# NHK2016mother.net
KiCad netlist of a schematic drawn in EAGLE
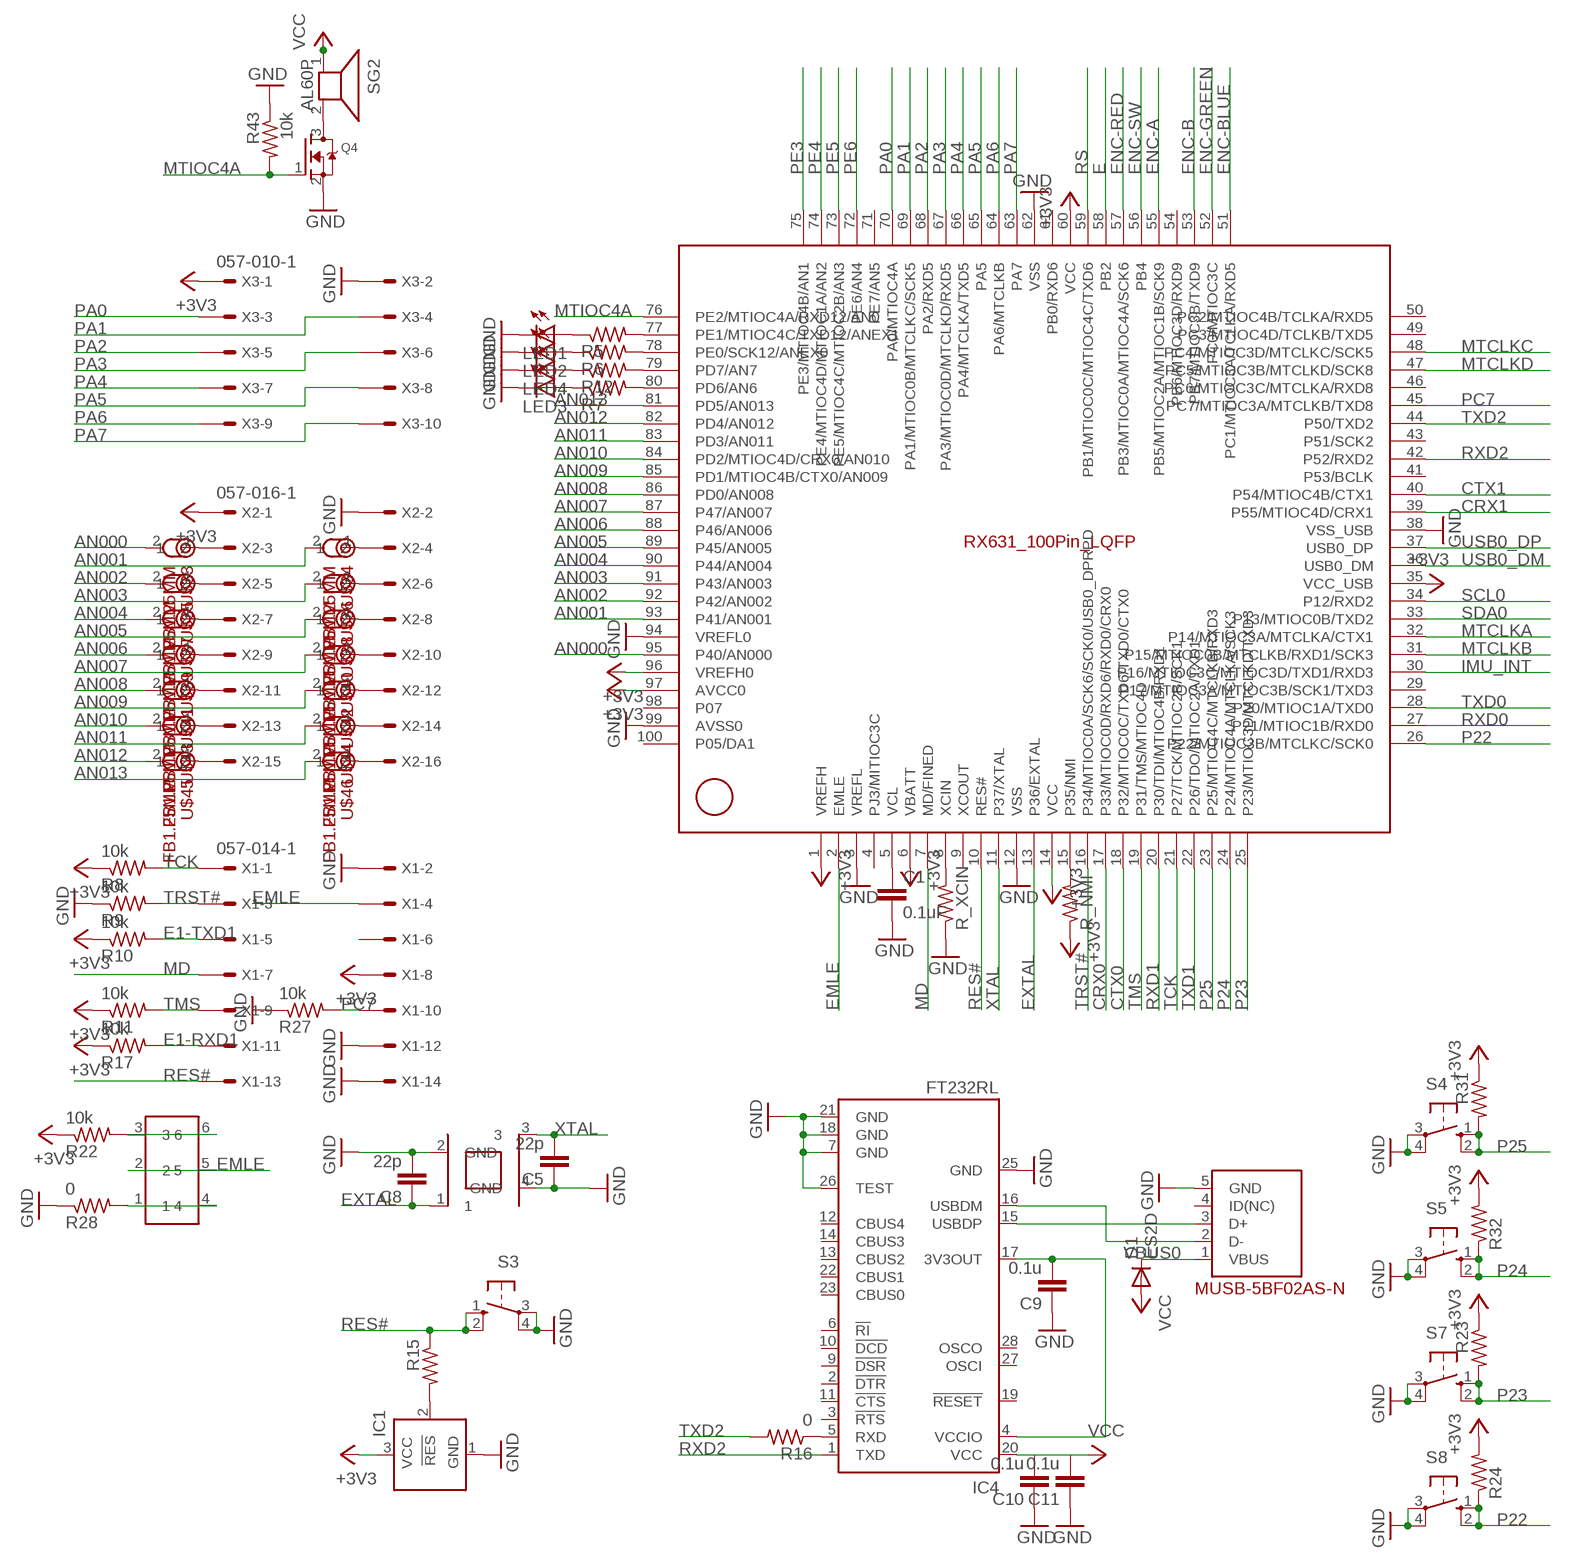
[diagram p0: schematic, sheet 1, part 1 of 2]
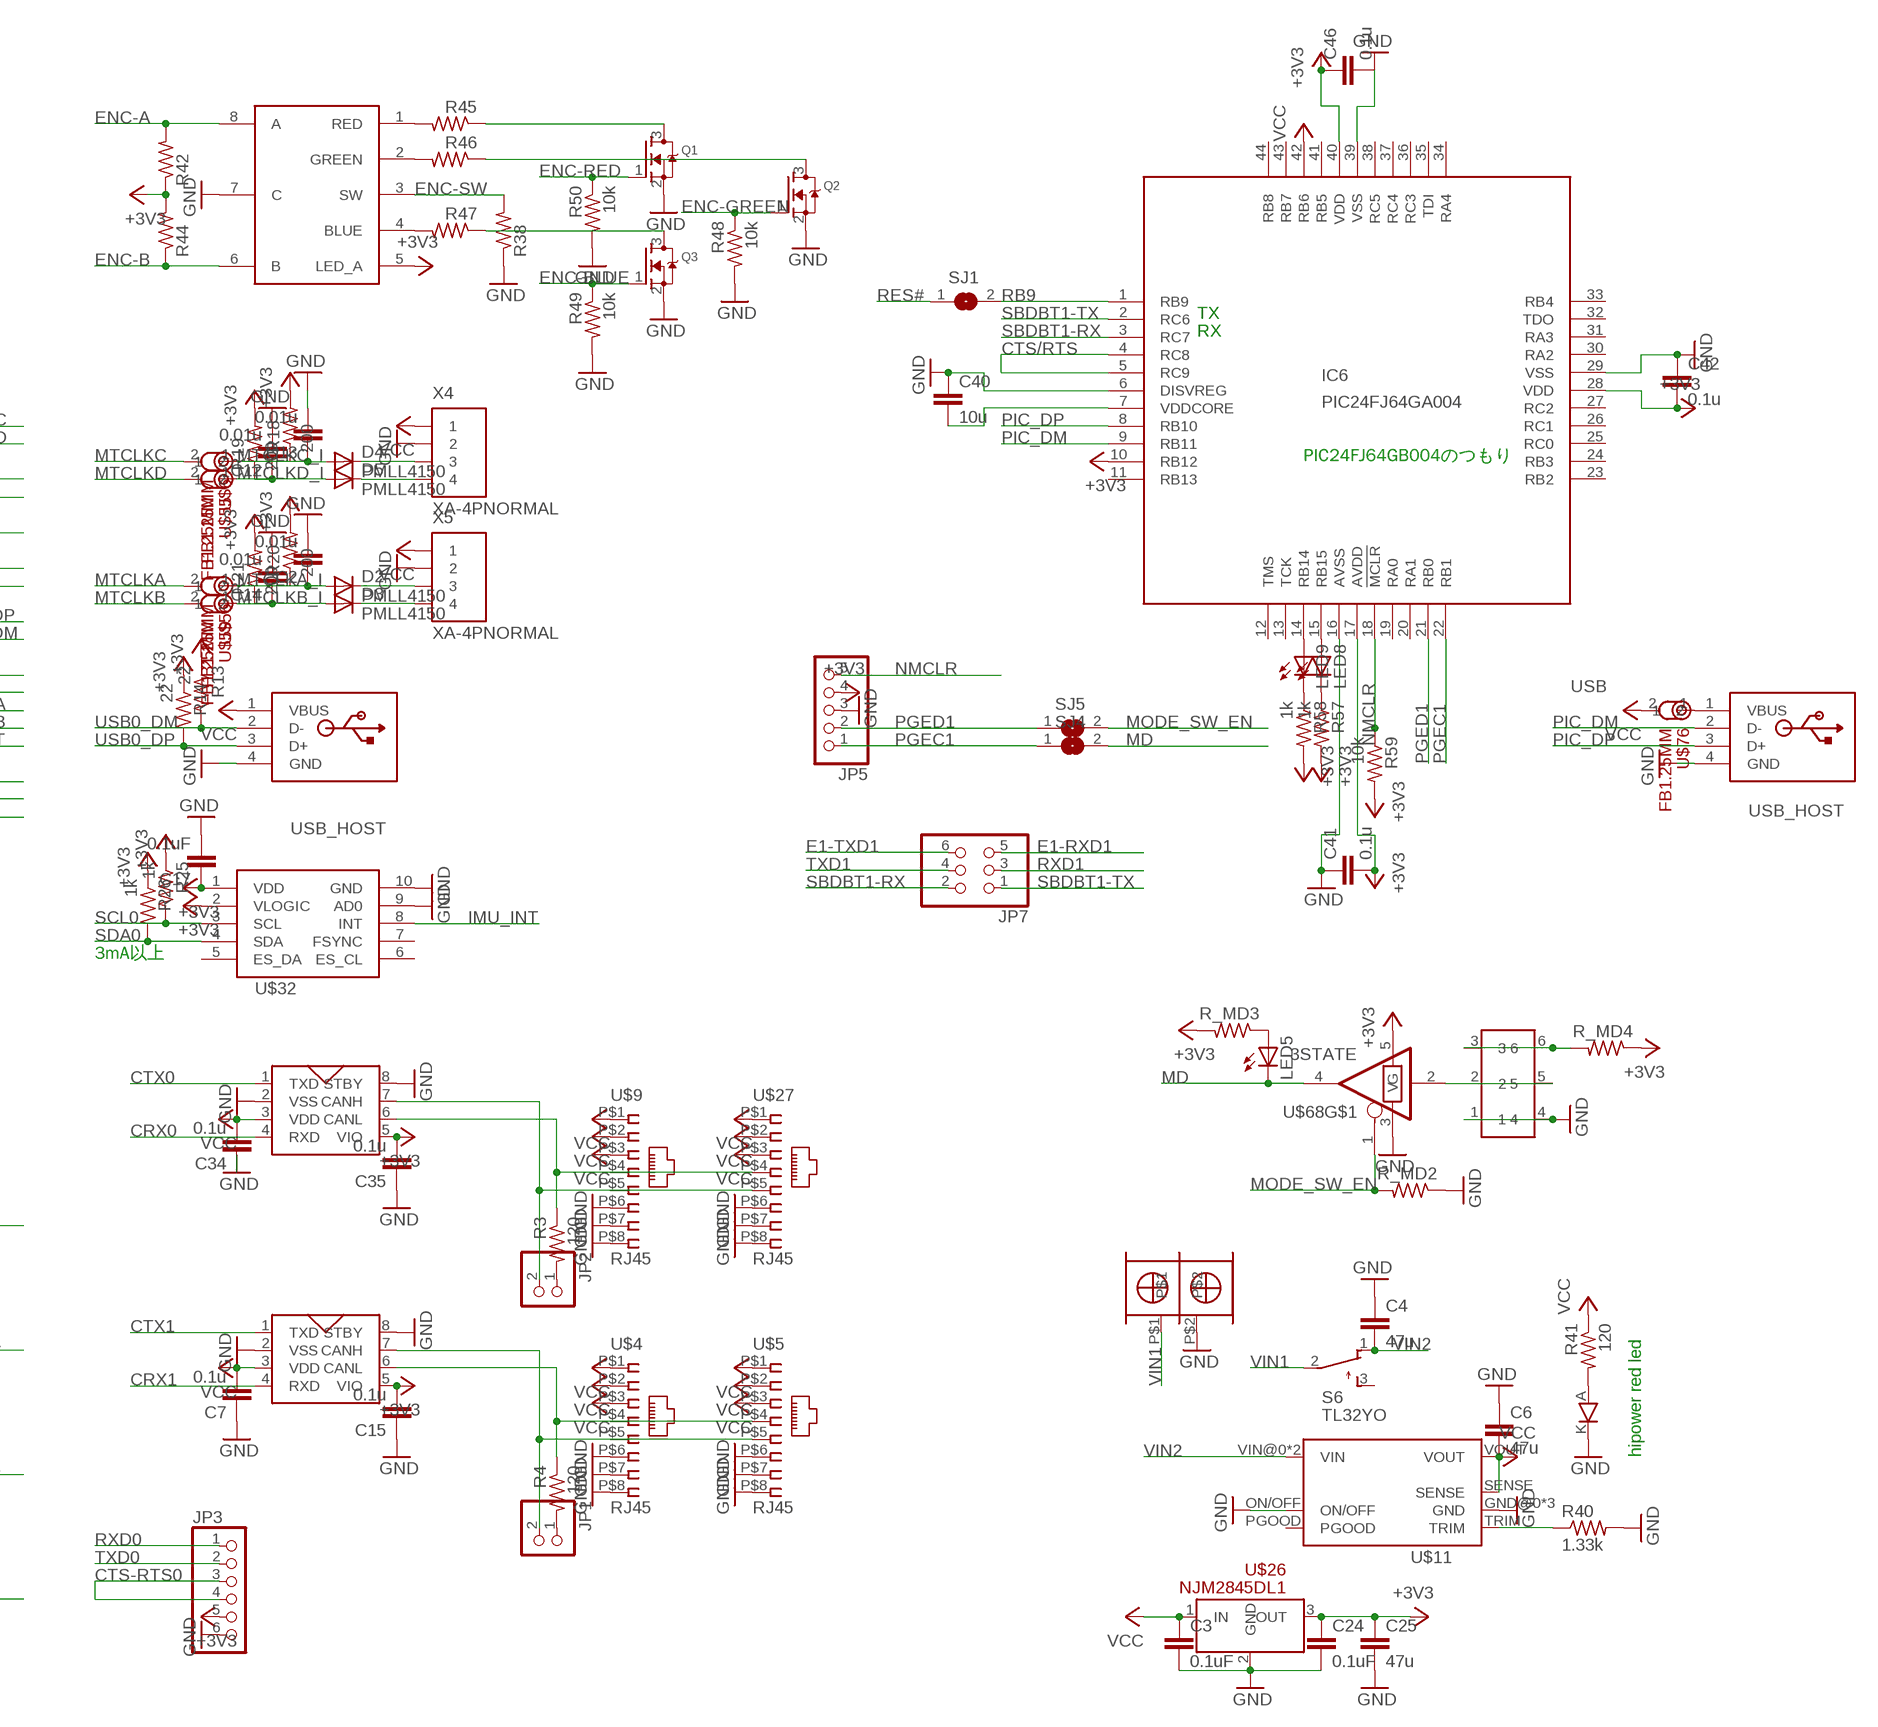
[diagram p1: schematic, sheet 1, part 2 of 2]

(export (version "E")
  (design (tool "Eeschema 10.0.6"))
  (components
    (comp (ref "C1")
      (value "0.1uF")
      (footprint "eagle-import:C0603K")
      (libsource (lib "eagle-import") (part "C-EUC0603K"))
    )
    (comp (ref "C2")
      (value "0.01u")
      (footprint "eagle-import:C0402")
      (libsource (lib "eagle-import") (part "C-EUC0402"))
    )
    (comp (ref "C3")
      (value "0.1uF")
      (footprint "eagle-import:C0603K")
      (libsource (lib "eagle-import") (part "C-EUC0603K"))
    )
    (comp (ref "C4")
      (value "47u")
      (footprint "eagle-import:C3225")
      (libsource (lib "eagle-import") (part "C-EUC3225"))
    )
    (comp (ref "C5")
      (value "22p")
      (footprint "eagle-import:C0603K")
      (libsource (lib "eagle-import") (part "C-EUC0603K"))
    )
    (comp (ref "C6")
      (value "47u")
      (footprint "eagle-import:C3225")
      (libsource (lib "eagle-import") (part "C-EUC3225"))
    )
    (comp (ref "C7")
      (value "0.1u")
      (footprint "eagle-import:C0402")
      (libsource (lib "eagle-import") (part "C-EUC0402"))
    )
    (comp (ref "C8")
      (value "22p")
      (footprint "eagle-import:C0603K")
      (libsource (lib "eagle-import") (part "C-EUC0603K"))
    )
    (comp (ref "C9")
      (value "0.1u")
      (footprint "eagle-import:C0402")
      (libsource (lib "eagle-import") (part "C-EUC0402"))
    )
    (comp (ref "C10")
      (value "0.1u")
      (footprint "eagle-import:C0402")
      (libsource (lib "eagle-import") (part "C-EUC0402"))
    )
    (comp (ref "C11")
      (value "0.1u")
      (footprint "eagle-import:C0402")
      (libsource (lib "eagle-import") (part "C-EUC0402"))
    )
    (comp (ref "C12")
      (value "0.01u")
      (footprint "eagle-import:C0402")
      (libsource (lib "eagle-import") (part "C-EUC0402"))
    )
    (comp (ref "C13")
      (value "0.01u")
      (footprint "eagle-import:C0402")
      (libsource (lib "eagle-import") (part "C-EUC0402"))
    )
    (comp (ref "C14")
      (value "0.01u")
      (footprint "eagle-import:C0402")
      (libsource (lib "eagle-import") (part "C-EUC0402"))
    )
    (comp (ref "C15")
      (value "0.1u")
      (footprint "eagle-import:C0402")
      (libsource (lib "eagle-import") (part "C-EUC0402"))
    )
    (comp (ref "C17")
      (value "0.1uF")
      (footprint "eagle-import:C0603K")
      (libsource (lib "eagle-import") (part "C-EUC0603K"))
    )
    (comp (ref "C24")
      (value "0.1uF")
      (footprint "eagle-import:C0603K")
      (libsource (lib "eagle-import") (part "C-EUC0603K"))
    )
    (comp (ref "C25")
      (value "47u")
      (footprint "eagle-import:C3225")
      (libsource (lib "eagle-import") (part "C-EUC3225"))
    )
    (comp (ref "C34")
      (value "0.1u")
      (footprint "eagle-import:C0402")
      (libsource (lib "eagle-import") (part "C-EUC0402"))
    )
    (comp (ref "C35")
      (value "0.1u")
      (footprint "eagle-import:C0402")
      (libsource (lib "eagle-import") (part "C-EUC0402"))
    )
    (comp (ref "C40")
      (value "10u")
      (footprint "eagle-import:C0603K")
      (libsource (lib "eagle-import") (part "C-EUC0603K"))
    )
    (comp (ref "C41")
      (value "0.1u")
      (footprint "eagle-import:C0603K")
      (libsource (lib "eagle-import") (part "C-EUC0603K"))
    )
    (comp (ref "C42")
      (value "0.1u")
      (footprint "eagle-import:C0603K")
      (libsource (lib "eagle-import") (part "C-EUC0603K"))
    )
    (comp (ref "C46")
      (value "0.1u")
      (footprint "eagle-import:C0603K")
      (libsource (lib "eagle-import") (part "C-EUC0603K"))
    )
    (comp (ref "D1")
      (value "ES2D")
      (footprint "eagle-import:SMB")
      (libsource (lib "eagle-import") (part "ES2D"))
    )
    (comp (ref "D2")
      (value "PMLL4150")
      (footprint "eagle-import:SOD80C")
      (libsource (lib "eagle-import") (part "PMLL4150"))
    )
    (comp (ref "D3")
      (value "PMLL4150")
      (footprint "eagle-import:SOD80C")
      (libsource (lib "eagle-import") (part "PMLL4150"))
    )
    (comp (ref "D4")
      (value "PMLL4150")
      (footprint "eagle-import:SOD80C")
      (libsource (lib "eagle-import") (part "PMLL4150"))
    )
    (comp (ref "D5")
      (value "PMLL4150")
      (footprint "eagle-import:SOD80C")
      (libsource (lib "eagle-import") (part "PMLL4150"))
    )
    (comp (ref "IC1")
      (value "TCM809")
      (footprint "eagle-import:SOT23B-3")
      (fields (field (name "MF") "MICROCHIP") (field (name "MPN") "TCM809MENB713"))
      (libsource (lib "eagle-import") (part "TCM809"))
    )
    (comp (ref "IC4")
      (value "FT232RL")
      (footprint "eagle-import:SSOP28")
      (libsource (lib "eagle-import") (part "FT232RL"))
    )
    (comp (ref "IC6")
      (value "PIC24FJ64GA004")
      (footprint "eagle-import:TQFP44")
      (fields (field (name "MPN") "PIC24FJ64GA004-E/PT"))
      (libsource (lib "eagle-import") (part "PIC24FJ64GA004"))
    )
    (comp (ref "JP1")
      (value "PINHD-1X2")
      (footprint "eagle-import:1X02")
      (libsource (lib "eagle-import") (part "PINHD-1X2"))
    )
    (comp (ref "JP2")
      (value "PINHD-1X2")
      (footprint "eagle-import:1X02")
      (libsource (lib "eagle-import") (part "PINHD-1X2"))
    )
    (comp (ref "JP3")
      (value "PINHD-1X6")
      (footprint "eagle-import:1X06")
      (libsource (lib "eagle-import") (part "PINHD-1X6"))
    )
    (comp (ref "JP5")
      (value "PINHD-1X5")
      (footprint "eagle-import:1X05")
      (libsource (lib "eagle-import") (part "PINHD-1X5"))
    )
    (comp (ref "JP7")
      (value "PINHD-2X3")
      (footprint "eagle-import:2X03")
      (libsource (lib "eagle-import") (part "PINHD-2X3"))
    )
    (comp (ref "LED1")
      (value "LEDSML0805")
      (footprint "eagle-import:SML0805")
      (libsource (lib "eagle-import") (part "LEDSML0805"))
    )
    (comp (ref "LED2")
      (value "LEDSML0805")
      (footprint "eagle-import:SML0805")
      (libsource (lib "eagle-import") (part "LEDSML0805"))
    )
    (comp (ref "LED3")
      (value "LEDSML0805")
      (footprint "eagle-import:SML0805")
      (libsource (lib "eagle-import") (part "LEDSML0805"))
    )
    (comp (ref "LED4")
      (value "LEDSML0805")
      (footprint "eagle-import:SML0805")
      (libsource (lib "eagle-import") (part "LEDSML0805"))
    )
    (comp (ref "LED5")
      (value "LEDSML0805")
      (footprint "eagle-import:SML0805")
      (libsource (lib "eagle-import") (part "LEDSML0805"))
    )
    (comp (ref "LED8")
      (value "LEDSML0805")
      (footprint "eagle-import:SML0805")
      (libsource (lib "eagle-import") (part "LEDSML0805"))
    )
    (comp (ref "LED9")
      (value "LEDSML0805")
      (footprint "eagle-import:SML0805")
      (libsource (lib "eagle-import") (part "LEDSML0805"))
    )
    (comp (ref "Q1")
      (value "MOSFET-NREFLOW")
      (footprint "eagle-import:SOT23")
      (libsource (lib "eagle-import") (part "MOSFET-NREFLOW"))
    )
    (comp (ref "Q2")
      (value "MOSFET-NREFLOW")
      (footprint "eagle-import:SOT23")
      (libsource (lib "eagle-import") (part "MOSFET-NREFLOW"))
    )
    (comp (ref "Q3")
      (value "MOSFET-NREFLOW")
      (footprint "eagle-import:SOT23")
      (libsource (lib "eagle-import") (part "MOSFET-NREFLOW"))
    )
    (comp (ref "Q4")
      (value "MOSFET-NREFLOW")
      (footprint "eagle-import:SOT23")
      (libsource (lib "eagle-import") (part "MOSFET-NREFLOW"))
    )
    (comp (ref "R3")
      (value "120")
      (footprint "eagle-import:MINI_MELF-0102W")
      (libsource (lib "eagle-import") (part "R-US_MELF0102W"))
    )
    (comp (ref "R4")
      (value "120")
      (footprint "eagle-import:MINI_MELF-0102W")
      (libsource (lib "eagle-import") (part "R-US_MELF0102W"))
    )
    (comp (ref "R5")
      (value "R-US_MELF0102W")
      (footprint "eagle-import:MINI_MELF-0102W")
      (libsource (lib "eagle-import") (part "R-US_MELF0102W"))
    )
    (comp (ref "R6")
      (value "R-US_MELF0102W")
      (footprint "eagle-import:MINI_MELF-0102W")
      (libsource (lib "eagle-import") (part "R-US_MELF0102W"))
    )
    (comp (ref "R7")
      (value "R-US_MELF0102W")
      (footprint "eagle-import:MINI_MELF-0102W")
      (libsource (lib "eagle-import") (part "R-US_MELF0102W"))
    )
    (comp (ref "R8")
      (value "10k")
      (footprint "eagle-import:MINI_MELF-0102W")
      (libsource (lib "eagle-import") (part "R-US_MELF0102W"))
    )
    (comp (ref "R9")
      (value "10k")
      (footprint "eagle-import:MINI_MELF-0102W")
      (libsource (lib "eagle-import") (part "R-US_MELF0102W"))
    )
    (comp (ref "R10")
      (value "10k")
      (footprint "eagle-import:MINI_MELF-0102W")
      (libsource (lib "eagle-import") (part "R-US_MELF0102W"))
    )
    (comp (ref "R11")
      (value "10k")
      (footprint "eagle-import:MINI_MELF-0102W")
      (libsource (lib "eagle-import") (part "R-US_MELF0102W"))
    )
    (comp (ref "R12")
      (value "R-US_MELF0102W")
      (footprint "eagle-import:MINI_MELF-0102W")
      (libsource (lib "eagle-import") (part "R-US_MELF0102W"))
    )
    (comp (ref "R13")
      (value "22")
      (footprint "eagle-import:MINI_MELF-0102W")
      (libsource (lib "eagle-import") (part "R-US_MELF0102W"))
    )
    (comp (ref "R14")
      (value "22")
      (footprint "eagle-import:MINI_MELF-0102W")
      (libsource (lib "eagle-import") (part "R-US_MELF0102W"))
    )
    (comp (ref "R15")
      (value "R-US_MELF0102W")
      (footprint "eagle-import:MINI_MELF-0102W")
      (libsource (lib "eagle-import") (part "R-US_MELF0102W"))
    )
    (comp (ref "R16")
      (value "0")
      (footprint "eagle-import:MINI_MELF-0102W")
      (libsource (lib "eagle-import") (part "R-US_MELF0102W"))
    )
    (comp (ref "R17")
      (value "10k")
      (footprint "eagle-import:MINI_MELF-0102W")
      (libsource (lib "eagle-import") (part "R-US_MELF0102W"))
    )
    (comp (ref "R18")
      (value "200")
      (footprint "eagle-import:MINI_MELF-0102W")
      (libsource (lib "eagle-import") (part "R-US_MELF0102W"))
    )
    (comp (ref "R19")
      (value "200")
      (footprint "eagle-import:MINI_MELF-0102W")
      (libsource (lib "eagle-import") (part "R-US_MELF0102W"))
    )
    (comp (ref "R20")
      (value "200")
      (footprint "eagle-import:MINI_MELF-0102W")
      (libsource (lib "eagle-import") (part "R-US_MELF0102W"))
    )
    (comp (ref "R21")
      (value "200")
      (footprint "eagle-import:MINI_MELF-0102W")
      (libsource (lib "eagle-import") (part "R-US_MELF0102W"))
    )
    (comp (ref "R22")
      (value "10k")
      (footprint "eagle-import:MINI_MELF-0102W")
      (libsource (lib "eagle-import") (part "R-US_MELF0102W"))
    )
    (comp (ref "R23")
      (value "R-US_MELF0102W")
      (footprint "eagle-import:MINI_MELF-0102W")
      (libsource (lib "eagle-import") (part "R-US_MELF0102W"))
    )
    (comp (ref "R24")
      (value "R-US_MELF0102W")
      (footprint "eagle-import:MINI_MELF-0102W")
      (libsource (lib "eagle-import") (part "R-US_MELF0102W"))
    )
    (comp (ref "R25")
      (value "1k")
      (footprint "eagle-import:MINI_MELF-0102W")
      (libsource (lib "eagle-import") (part "R-US_MELF0102W"))
    )
    (comp (ref "R26")
      (value "1k")
      (footprint "eagle-import:MINI_MELF-0102W")
      (libsource (lib "eagle-import") (part "R-US_MELF0102W"))
    )
    (comp (ref "R27")
      (value "10k")
      (footprint "eagle-import:MINI_MELF-0102W")
      (libsource (lib "eagle-import") (part "R-US_MELF0102W"))
    )
    (comp (ref "R28")
      (value "0")
      (footprint "eagle-import:MINI_MELF-0102W")
      (libsource (lib "eagle-import") (part "R-US_MELF0102W"))
    )
    (comp (ref "R31")
      (value "R-US_MELF0102W")
      (footprint "eagle-import:MINI_MELF-0102W")
      (libsource (lib "eagle-import") (part "R-US_MELF0102W"))
    )
    (comp (ref "R32")
      (value "R-US_MELF0102W")
      (footprint "eagle-import:MINI_MELF-0102W")
      (libsource (lib "eagle-import") (part "R-US_MELF0102W"))
    )
    (comp (ref "R38")
      (value "R-US_MELF0102W")
      (footprint "eagle-import:MINI_MELF-0102W")
      (libsource (lib "eagle-import") (part "R-US_MELF0102W"))
    )
    (comp (ref "R40")
      (value "1.33k")
      (footprint "eagle-import:MINI_MELF-0102W")
      (libsource (lib "eagle-import") (part "R-US_MELF0102W"))
    )
    (comp (ref "R41")
      (value "120")
      (footprint "eagle-import:MINI_MELF-0102W")
      (libsource (lib "eagle-import") (part "R-US_MELF0102W"))
    )
    (comp (ref "R42")
      (value "R-US_MELF0102W")
      (footprint "eagle-import:MINI_MELF-0102W")
      (libsource (lib "eagle-import") (part "R-US_MELF0102W"))
    )
    (comp (ref "R43")
      (value "10k")
      (footprint "eagle-import:MINI_MELF-0102W")
      (libsource (lib "eagle-import") (part "R-US_MELF0102W"))
    )
    (comp (ref "R44")
      (value "R-US_MELF0102W")
      (footprint "eagle-import:MINI_MELF-0102W")
      (libsource (lib "eagle-import") (part "R-US_MELF0102W"))
    )
    (comp (ref "R45")
      (value "R-US_MELF0102W")
      (footprint "eagle-import:MINI_MELF-0102W")
      (libsource (lib "eagle-import") (part "R-US_MELF0102W"))
    )
    (comp (ref "R46")
      (value "R-US_MELF0102W")
      (footprint "eagle-import:MINI_MELF-0102W")
      (libsource (lib "eagle-import") (part "R-US_MELF0102W"))
    )
    (comp (ref "R47")
      (value "R-US_MELF0102W")
      (footprint "eagle-import:MINI_MELF-0102W")
      (libsource (lib "eagle-import") (part "R-US_MELF0102W"))
    )
    (comp (ref "R48")
      (value "10k")
      (footprint "eagle-import:MINI_MELF-0102W")
      (libsource (lib "eagle-import") (part "R-US_MELF0102W"))
    )
    (comp (ref "R49")
      (value "10k")
      (footprint "eagle-import:MINI_MELF-0102W")
      (libsource (lib "eagle-import") (part "R-US_MELF0102W"))
    )
    (comp (ref "R50")
      (value "10k")
      (footprint "eagle-import:MINI_MELF-0102W")
      (libsource (lib "eagle-import") (part "R-US_MELF0102W"))
    )
    (comp (ref "R57")
      (value "1k")
      (footprint "eagle-import:MINI_MELF-0102W")
      (libsource (lib "eagle-import") (part "R-US_MELF0102W"))
    )
    (comp (ref "R58")
      (value "1k")
      (footprint "eagle-import:MINI_MELF-0102W")
      (libsource (lib "eagle-import") (part "R-US_MELF0102W"))
    )
    (comp (ref "R59")
      (value "10k")
      (footprint "eagle-import:MINI_MELF-0102W")
      (libsource (lib "eagle-import") (part "R-US_MELF0102W"))
    )
    (comp (ref "R_MD2")
      (value "R-US_MELF0102W")
      (footprint "eagle-import:MINI_MELF-0102W")
      (libsource (lib "eagle-import") (part "R-US_MELF0102W"))
    )
    (comp (ref "R_MD3")
      (value "R-US_MELF0102W")
      (footprint "eagle-import:MINI_MELF-0102W")
      (libsource (lib "eagle-import") (part "R-US_MELF0102W"))
    )
    (comp (ref "R_MD4")
      (value "R-US_MELF0102W")
      (footprint "eagle-import:MINI_MELF-0102W")
      (libsource (lib "eagle-import") (part "R-US_MELF0102W"))
    )
    (comp (ref "R_NMI")
      (value "R-US_MELF0102W")
      (footprint "eagle-import:MINI_MELF-0102W")
      (libsource (lib "eagle-import") (part "R-US_MELF0102W"))
    )
    (comp (ref "R_XCIN")
      (value "R-US_MELF0102W")
      (footprint "eagle-import:MINI_MELF-0102W")
      (libsource (lib "eagle-import") (part "R-US_MELF0102W"))
    )
    (comp (ref "S3")
      (value "10-XX")
      (footprint "eagle-import:B3F-10XX")
      (fields (field (name "MPN") "B3F-1000"))
      (libsource (lib "eagle-import") (part "10-XX"))
    )
    (comp (ref "S4")
      (value "10-XX")
      (footprint "eagle-import:B3F-10XX")
      (fields (field (name "MPN") "B3F-1000"))
      (libsource (lib "eagle-import") (part "10-XX"))
    )
    (comp (ref "S5")
      (value "10-XX")
      (footprint "eagle-import:B3F-10XX")
      (fields (field (name "MPN") "B3F-1000"))
      (libsource (lib "eagle-import") (part "10-XX"))
    )
    (comp (ref "S6")
      (value "TL32YO")
      (footprint "eagle-import:TL3XYO")
      (libsource (lib "eagle-import") (part "TL32YO"))
    )
    (comp (ref "S7")
      (value "10-XX")
      (footprint "eagle-import:B3F-10XX")
      (fields (field (name "MPN") "B3F-1000"))
      (libsource (lib "eagle-import") (part "10-XX"))
    )
    (comp (ref "S8")
      (value "10-XX")
      (footprint "eagle-import:B3F-10XX")
      (fields (field (name "MPN") "B3F-1000"))
      (libsource (lib "eagle-import") (part "10-XX"))
    )
    (comp (ref "SG2")
      (value "AL60P")
      (footprint "eagle-import:AL60P")
      (libsource (lib "eagle-import") (part "AL60P"))
    )
    (comp (ref "SJ1") (value "SJ") (footprint "eagle-import:SJ") (libsource (lib "eagle-import") (part "SJ")))
    (comp (ref "SJ4") (value "SJ") (footprint "eagle-import:SJ") (libsource (lib "eagle-import") (part "SJ")))
    (comp (ref "SJ5") (value "SJ") (footprint "eagle-import:SJ") (libsource (lib "eagle-import") (part "SJ")))
    (comp (ref "U$1")
      (value "R5F5631FDDFP")
      (footprint "eagle-import:LQFP100")
      (libsource (lib "eagle-import") (part "R5F5631FDDFP"))
    )
    (comp (ref "U$2")
      (value "MUSB-5BF02AS-N")
      (footprint "eagle-import:MUSB-5BF02AS-N")
      (libsource (lib "eagle-import") (part "MUSB-5BF02AS-N"))
    )
    (comp (ref "U$3")
      (value "MCP2562")
      (footprint "eagle-import:MCP2562")
      (libsource (lib "eagle-import") (part "MCP2562"))
    )
    (comp (ref "U$4")
      (value "RJ45")
      (footprint "eagle-import:RJ45")
      (libsource (lib "eagle-import") (part "RJ45"))
    )
    (comp (ref "U$5")
      (value "RJ45")
      (footprint "eagle-import:RJ45")
      (libsource (lib "eagle-import") (part "RJ45"))
    )
    (comp (ref "U$6")
      (value "FB1.25MM")
      (footprint "eagle-import:2012")
      (libsource (lib "eagle-import") (part "FB1.25MM"))
    )
    (comp (ref "U$7")
      (value "SSSS2")
      (footprint "eagle-import:SSSS2")
      (libsource (lib "eagle-import") (part "SSSS2"))
    )
    (comp (ref "U$8")
      (value "ＦＲ１１０５Ｗ－ＴＲ")
      (footprint "eagle-import:ＦＲ１１０５Ｗ－ＴＲ")
      (libsource (lib "eagle-import") (part "ＦＲ１１０５Ｗ－ＴＲ"))
    )
    (comp (ref "U$9")
      (value "RJ45")
      (footprint "eagle-import:RJ45")
      (libsource (lib "eagle-import") (part "RJ45"))
    )
    (comp (ref "U$10")
      (value "TERMINAL")
      (footprint "eagle-import:TERMINAL")
      (libsource (lib "eagle-import") (part "TERMINAL"))
    )
    (comp (ref "U$11")
      (value "OKL_T6_W12")
      (footprint "eagle-import:OKL_T6_W12")
      (libsource (lib "eagle-import") (part "OKL_T6_W12"))
    )
    (comp (ref "U$17")
      (value "MCP2562")
      (footprint "eagle-import:MCP2562")
      (libsource (lib "eagle-import") (part "MCP2562"))
    )
    (comp (ref "U$26")
      (value "NJM2845DL1")
      (footprint "eagle-import:TO-252-3-L1")
      (libsource (lib "eagle-import") (part "NJM2845DL1"))
    )
    (comp (ref "U$27")
      (value "RJ45")
      (footprint "eagle-import:RJ45")
      (libsource (lib "eagle-import") (part "RJ45"))
    )
    (comp (ref "U$29")
      (value "USB_A")
      (footprint "eagle-import:USB_A")
      (libsource (lib "eagle-import") (part "USB_A"))
    )
    (comp (ref "U$32")
      (value "MPU9150")
      (footprint "eagle-import:MPU9150")
      (libsource (lib "eagle-import") (part "MPU9150"))
    )
    (comp (ref "U$33")
      (value "FB1.25MM")
      (footprint "eagle-import:2012")
      (libsource (lib "eagle-import") (part "FB1.25MM"))
    )
    (comp (ref "U$34")
      (value "FB1.25MM")
      (footprint "eagle-import:2012")
      (libsource (lib "eagle-import") (part "FB1.25MM"))
    )
    (comp (ref "U$35")
      (value "FB1.25MM")
      (footprint "eagle-import:2012")
      (libsource (lib "eagle-import") (part "FB1.25MM"))
    )
    (comp (ref "U$36")
      (value "FB1.25MM")
      (footprint "eagle-import:2012")
      (libsource (lib "eagle-import") (part "FB1.25MM"))
    )
    (comp (ref "U$37")
      (value "FB1.25MM")
      (footprint "eagle-import:2012")
      (libsource (lib "eagle-import") (part "FB1.25MM"))
    )
    (comp (ref "U$38")
      (value "FB1.25MM")
      (footprint "eagle-import:2012")
      (libsource (lib "eagle-import") (part "FB1.25MM"))
    )
    (comp (ref "U$39")
      (value "FB1.25MM")
      (footprint "eagle-import:2012")
      (libsource (lib "eagle-import") (part "FB1.25MM"))
    )
    (comp (ref "U$40")
      (value "FB1.25MM")
      (footprint "eagle-import:2012")
      (libsource (lib "eagle-import") (part "FB1.25MM"))
    )
    (comp (ref "U$41")
      (value "FB1.25MM")
      (footprint "eagle-import:2012")
      (libsource (lib "eagle-import") (part "FB1.25MM"))
    )
    (comp (ref "U$42")
      (value "FB1.25MM")
      (footprint "eagle-import:2012")
      (libsource (lib "eagle-import") (part "FB1.25MM"))
    )
    (comp (ref "U$43")
      (value "FB1.25MM")
      (footprint "eagle-import:2012")
      (libsource (lib "eagle-import") (part "FB1.25MM"))
    )
    (comp (ref "U$44")
      (value "FB1.25MM")
      (footprint "eagle-import:2012")
      (libsource (lib "eagle-import") (part "FB1.25MM"))
    )
    (comp (ref "U$45")
      (value "FB1.25MM")
      (footprint "eagle-import:2012")
      (libsource (lib "eagle-import") (part "FB1.25MM"))
    )
    (comp (ref "U$46")
      (value "FB1.25MM")
      (footprint "eagle-import:2012")
      (libsource (lib "eagle-import") (part "FB1.25MM"))
    )
    (comp (ref "U$55")
      (value "FB1.25MM")
      (footprint "eagle-import:2012")
      (libsource (lib "eagle-import") (part "FB1.25MM"))
    )
    (comp (ref "U$56")
      (value "FB1.25MM")
      (footprint "eagle-import:2012")
      (libsource (lib "eagle-import") (part "FB1.25MM"))
    )
    (comp (ref "U$58")
      (value "EC12PLRGBSDVBF")
      (footprint "eagle-import:EC12PLRGBSDVBF")
      (libsource (lib "eagle-import") (part "EC12PLRGBSDVBF"))
    )
    (comp (ref "U$59")
      (value "FB1.25MM")
      (footprint "eagle-import:2012")
      (libsource (lib "eagle-import") (part "FB1.25MM"))
    )
    (comp (ref "U$61")
      (value "FA238V")
      (footprint "eagle-import:FA238V")
      (libsource (lib "eagle-import") (part "FA238V"))
    )
    (comp (ref "U$68")
      (value "3STATE")
      (footprint "eagle-import:SOT23-5")
      (libsource (lib "eagle-import") (part "3STATE"))
    )
    (comp (ref "U$75")
      (value "USB_A")
      (footprint "eagle-import:USB_A")
      (libsource (lib "eagle-import") (part "USB_A"))
    )
    (comp (ref "U$76")
      (value "FB1.25MM")
      (footprint "eagle-import:2012")
      (libsource (lib "eagle-import") (part "FB1.25MM"))
    )
    (comp (ref "U$82")
      (value "SSSS2")
      (footprint "eagle-import:SSSS2")
      (libsource (lib "eagle-import") (part "SSSS2"))
    )
    (comp (ref "X1")
      (value "057-014-1")
      (footprint "eagle-import:057-014-1")
      (libsource (lib "eagle-import") (part "057-014-1"))
    )
    (comp (ref "X2")
      (value "057-016-1")
      (footprint "eagle-import:057-016-1")
      (libsource (lib "eagle-import") (part "057-016-1"))
    )
    (comp (ref "X3")
      (value "057-010-1")
      (footprint "eagle-import:057-010-1")
      (libsource (lib "eagle-import") (part "057-010-1"))
    )
    (comp (ref "X4")
      (value "XA-4PNORMAL")
      (footprint "eagle-import:XA-4P")
      (libsource (lib "eagle-import") (part "XA-4PNORMAL"))
    )
    (comp (ref "X5")
      (value "XA-4PNORMAL")
      (footprint "eagle-import:XA-4P")
      (libsource (lib "eagle-import") (part "XA-4PNORMAL"))
    )
  )
  (nets
    (net (code "1") (name "+3V3") (class "Default")
      (node (ref "C15") (pin "2") (pinfunction "2_2") (pintype "passive"))
      (node (ref "C17") (pin "1") (pinfunction "1_1") (pintype "passive"))
      (node (ref "C24") (pin "1") (pinfunction "1_1") (pintype "passive"))
      (node (ref "C25") (pin "1") (pinfunction "1_1") (pintype "passive"))
      (node (ref "C35") (pin "2") (pinfunction "2_2") (pintype "passive"))
      (node (ref "C41") (pin "2") (pinfunction "2_2") (pintype "passive"))
      (node (ref "C42") (pin "2") (pinfunction "2_2") (pintype "passive"))
      (node (ref "C46") (pin "1") (pinfunction "1_1") (pintype "passive"))
      (node (ref "IC1") (pin "3") (pinfunction "VCC_3") (pintype "power_in"))
      (node (ref "IC6") (pin "10") (pinfunction "RB12_10") (pintype "bidirectional"))
      (node (ref "IC6") (pin "17") (pinfunction "AVDD_17") (pintype "power_in"))
      (node (ref "IC6") (pin "28") (pinfunction "VDD_28") (pintype "power_in"))
      (node (ref "IC6") (pin "40") (pinfunction "VDD_40") (pintype "power_in"))
      (node (ref "JP3") (pin "5") (pinfunction "5_5") (pintype "passive"))
      (node (ref "JP5") (pin "4") (pinfunction "4_4") (pintype "passive"))
      (node (ref "R10") (pin "1") (pinfunction "1_1") (pintype "passive"))
      (node (ref "R11") (pin "1") (pinfunction "1_1") (pintype "passive"))
      (node (ref "R13") (pin "1") (pinfunction "1_1") (pintype "passive"))
      (node (ref "R14") (pin "1") (pinfunction "1_1") (pintype "passive"))
      (node (ref "R17") (pin "1") (pinfunction "1_1") (pintype "passive"))
      (node (ref "R18") (pin "2") (pinfunction "2_2") (pintype "passive"))
      (node (ref "R19") (pin "2") (pinfunction "2_2") (pintype "passive"))
      (node (ref "R20") (pin "2") (pinfunction "2_2") (pintype "passive"))
      (node (ref "R21") (pin "2") (pinfunction "2_2") (pintype "passive"))
      (node (ref "R22") (pin "1") (pinfunction "1_1") (pintype "passive"))
      (node (ref "R23") (pin "1") (pinfunction "1_1") (pintype "passive"))
      (node (ref "R24") (pin "2") (pinfunction "2_2") (pintype "passive"))
      (node (ref "R25") (pin "1") (pinfunction "1_1") (pintype "passive"))
      (node (ref "R26") (pin "1") (pinfunction "1_1") (pintype "passive"))
      (node (ref "R31") (pin "1") (pinfunction "1_1") (pintype "passive"))
      (node (ref "R32") (pin "2") (pinfunction "2_2") (pintype "passive"))
      (node (ref "R42") (pin "1") (pinfunction "1_1") (pintype "passive"))
      (node (ref "R44") (pin "2") (pinfunction "2_2") (pintype "passive"))
      (node (ref "R57") (pin "2") (pinfunction "2_2") (pintype "passive"))
      (node (ref "R58") (pin "2") (pinfunction "2_2") (pintype "passive"))
      (node (ref "R59") (pin "2") (pinfunction "2_2") (pintype "passive"))
      (node (ref "R8") (pin "1") (pinfunction "1_1") (pintype "passive"))
      (node (ref "R_MD3") (pin "2") (pinfunction "2_2") (pintype "passive"))
      (node (ref "R_MD4") (pin "1") (pinfunction "1_1") (pintype "passive"))
      (node (ref "R_NMI") (pin "1") (pinfunction "1_1") (pintype "passive"))
      (node (ref "U$1") (pin "1") (pinfunction "VREFH_1") (pintype "bidirectional"))
      (node (ref "U$1") (pin "14") (pinfunction "VCC_14") (pintype "bidirectional"))
      (node (ref "U$1") (pin "35") (pinfunction "VCC_USB_35") (pintype "bidirectional"))
      (node (ref "U$1") (pin "6") (pinfunction "VBATT_6") (pintype "bidirectional"))
      (node (ref "U$1") (pin "60") (pinfunction "VCC_60") (pintype "bidirectional"))
      (node (ref "U$1") (pin "96") (pinfunction "VREFH0_96") (pintype "bidirectional"))
      (node (ref "U$1") (pin "97") (pinfunction "AVCC0_97") (pintype "bidirectional"))
      (node (ref "U$17") (pin "5") (pinfunction "VIO_5") (pintype "power_in"))
      (node (ref "U$26") (pin "3") (pinfunction "OUT_3") (pintype "power_in"))
      (node (ref "U$3") (pin "5") (pinfunction "VIO_5") (pintype "power_in"))
      (node (ref "U$32") (pin "1") (pinfunction "VDD_1") (pintype "bidirectional"))
      (node (ref "U$32") (pin "2") (pinfunction "VLOGIC_2") (pintype "bidirectional"))
      (node (ref "U$58") (pin "5") (pinfunction "LED_A_5") (pintype "bidirectional"))
      (node (ref "U$68") (pin "5") (pinfunction "V_5") (pintype "bidirectional"))
      (node (ref "X1") (pin "8") (pinfunction "S_8") (pintype "passive"))
      (node (ref "X2") (pin "1") (pinfunction "S_1") (pintype "passive"))
      (node (ref "X3") (pin "1") (pinfunction "S_1") (pintype "passive"))
    )
    (net (code "2") (name "/AN000") (class "Default")
      (node (ref "U$1") (pin "95") (pinfunction "P40/AN000_95") (pintype "bidirectional"))
      (node (ref "U$33") (pin "2") (pinfunction "2_2") (pintype "passive"))
    )
    (net (code "3") (name "/AN001") (class "Default")
      (node (ref "U$1") (pin "93") (pinfunction "P41/AN001_93") (pintype "bidirectional"))
      (node (ref "U$34") (pin "2") (pinfunction "2_2") (pintype "passive"))
    )
    (net (code "4") (name "/AN002") (class "Default")
      (node (ref "U$1") (pin "92") (pinfunction "P42/AN002_92") (pintype "bidirectional"))
      (node (ref "U$35") (pin "2") (pinfunction "2_2") (pintype "passive"))
    )
    (net (code "5") (name "/AN003") (class "Default")
      (node (ref "U$1") (pin "91") (pinfunction "P43/AN003_91") (pintype "bidirectional"))
      (node (ref "U$36") (pin "2") (pinfunction "2_2") (pintype "passive"))
    )
    (net (code "6") (name "/AN004") (class "Default")
      (node (ref "U$1") (pin "90") (pinfunction "P44/AN004_90") (pintype "bidirectional"))
      (node (ref "U$37") (pin "2") (pinfunction "2_2") (pintype "passive"))
    )
    (net (code "7") (name "/AN005") (class "Default")
      (node (ref "U$1") (pin "89") (pinfunction "P45/AN005_89") (pintype "bidirectional"))
      (node (ref "U$38") (pin "2") (pinfunction "2_2") (pintype "passive"))
    )
    (net (code "8") (name "/AN006") (class "Default")
      (node (ref "U$1") (pin "88") (pinfunction "P46/AN006_88") (pintype "bidirectional"))
      (node (ref "U$39") (pin "2") (pinfunction "2_2") (pintype "passive"))
    )
    (net (code "9") (name "/AN007") (class "Default")
      (node (ref "U$1") (pin "87") (pinfunction "P47/AN007_87") (pintype "bidirectional"))
      (node (ref "U$40") (pin "2") (pinfunction "2_2") (pintype "passive"))
    )
    (net (code "10") (name "/AN008") (class "Default")
      (node (ref "U$1") (pin "86") (pinfunction "PD0/AN008_86") (pintype "bidirectional"))
      (node (ref "U$41") (pin "2") (pinfunction "2_2") (pintype "passive"))
    )
    (net (code "11") (name "/AN009") (class "Default")
      (node (ref "U$1") (pin "85") (pinfunction "PD1/MTIOC4B/CTX0/AN009_85") (pintype "bidirectional"))
      (node (ref "U$42") (pin "2") (pinfunction "2_2") (pintype "passive"))
    )
    (net (code "12") (name "/AN010") (class "Default")
      (node (ref "U$1") (pin "84") (pinfunction "PD2/MTIOC4D/CRX0/AN010_84") (pintype "bidirectional"))
      (node (ref "U$43") (pin "2") (pinfunction "2_2") (pintype "passive"))
    )
    (net (code "13") (name "/AN011") (class "Default")
      (node (ref "U$1") (pin "83") (pinfunction "PD3/AN011_83") (pintype "bidirectional"))
      (node (ref "U$44") (pin "2") (pinfunction "2_2") (pintype "passive"))
    )
    (net (code "14") (name "/AN012") (class "Default")
      (node (ref "U$1") (pin "82") (pinfunction "PD4/AN012_82") (pintype "bidirectional"))
      (node (ref "U$45") (pin "2") (pinfunction "2_2") (pintype "passive"))
    )
    (net (code "15") (name "/AN013") (class "Default")
      (node (ref "U$1") (pin "81") (pinfunction "PD5/AN013_81") (pintype "bidirectional"))
      (node (ref "U$46") (pin "2") (pinfunction "2_2") (pintype "passive"))
    )
    (net (code "16") (name "/CRX0") (class "Default")
      (node (ref "U$1") (pin "17") (pinfunction "P33/MTIOC0D/RXD6/RXD0/CRX0_17") (pintype "bidirectional"))
      (node (ref "U$17") (pin "4") (pinfunction "RXD_4") (pintype "bidirectional"))
    )
    (net (code "17") (name "/CRX1") (class "Default")
      (node (ref "U$1") (pin "39") (pinfunction "P55/MTIOC4D/CRX1_39") (pintype "bidirectional"))
      (node (ref "U$3") (pin "4") (pinfunction "RXD_4") (pintype "bidirectional"))
    )
    (net (code "18") (name "/CTS-RTS0") (class "Default")
      (node (ref "JP3") (pin "3") (pinfunction "3_3") (pintype "passive"))
      (node (ref "JP3") (pin "4") (pinfunction "4_4") (pintype "passive"))
    )
    (net (code "19") (name "/CTS{slash}RTS") (class "Default")
      (node (ref "IC6") (pin "4") (pinfunction "RC8_4") (pintype "bidirectional"))
      (node (ref "IC6") (pin "5") (pinfunction "RC9_5") (pintype "bidirectional"))
    )
    (net (code "20") (name "/CTX0") (class "Default")
      (node (ref "U$1") (pin "18") (pinfunction "P32/MTIOC0C/TXD6/TXD0/CTX0_18") (pintype "bidirectional"))
      (node (ref "U$17") (pin "1") (pinfunction "TXD_1") (pintype "bidirectional"))
    )
    (net (code "21") (name "/CTX1") (class "Default")
      (node (ref "U$1") (pin "40") (pinfunction "P54/MTIOC4B/CTX1_40") (pintype "bidirectional"))
      (node (ref "U$3") (pin "1") (pinfunction "TXD_1") (pintype "bidirectional"))
    )
    (net (code "22") (name "/E") (class "Default")
      (node (ref "U$1") (pin "58") (pinfunction "PB2_58") (pintype "bidirectional"))
    )
    (net (code "23") (name "/E1-RXD1") (class "Default")
      (node (ref "JP7") (pin "5") (pinfunction "5_5") (pintype "passive"))
      (node (ref "R17") (pin "2") (pinfunction "2_2") (pintype "passive"))
      (node (ref "X1") (pin "11") (pinfunction "S_11") (pintype "passive"))
    )
    (net (code "24") (name "/E1-TXD1") (class "Default")
      (node (ref "JP7") (pin "6") (pinfunction "6_6") (pintype "passive"))
      (node (ref "R10") (pin "2") (pinfunction "2_2") (pintype "passive"))
      (node (ref "X1") (pin "5") (pinfunction "S_5") (pintype "passive"))
    )
    (net (code "25") (name "/EMLE") (class "Default")
      (node (ref "U$1") (pin "2") (pinfunction "EMLE_2") (pintype "bidirectional"))
      (node (ref "U$7") (pin "2") (pinfunction "2_2") (pintype "bidirectional"))
      (node (ref "U$7") (pin "5") (pinfunction "5_5") (pintype "bidirectional"))
      (node (ref "X1") (pin "4") (pinfunction "S_4") (pintype "passive"))
    )
    (net (code "26") (name "/ENC-A") (class "Default")
      (node (ref "R42") (pin "2") (pinfunction "2_2") (pintype "passive"))
      (node (ref "U$1") (pin "55") (pinfunction "PB5/MTIOC2A/MTIOC1B/SCK9_55") (pintype "bidirectional"))
      (node (ref "U$58") (pin "8") (pinfunction "A_8") (pintype "bidirectional"))
    )
    (net (code "27") (name "/ENC-B") (class "Default")
      (node (ref "R44") (pin "1") (pinfunction "1_1") (pintype "passive"))
      (node (ref "U$1") (pin "53") (pinfunction "PB7/MTIOC3B/TXD9_53") (pintype "bidirectional"))
      (node (ref "U$58") (pin "6") (pinfunction "B_6") (pintype "bidirectional"))
    )
    (net (code "28") (name "/ENC-BLUE") (class "Default")
      (node (ref "Q3") (pin "1") (pinfunction "G_1") (pintype "bidirectional"))
      (node (ref "R49") (pin "1") (pinfunction "1_1") (pintype "passive"))
      (node (ref "U$1") (pin "51") (pinfunction "PC1/MTIOC3A/TCLKA/RXD5_51") (pintype "bidirectional"))
    )
    (net (code "29") (name "/ENC-GREEN") (class "Default")
      (node (ref "Q2") (pin "1") (pinfunction "G_1") (pintype "bidirectional"))
      (node (ref "R48") (pin "1") (pinfunction "1_1") (pintype "passive"))
      (node (ref "U$1") (pin "52") (pinfunction "PC0/MTIOC3C_52") (pintype "bidirectional"))
    )
    (net (code "30") (name "/ENC-RED") (class "Default")
      (node (ref "Q1") (pin "1") (pinfunction "G_1") (pintype "bidirectional"))
      (node (ref "R50") (pin "1") (pinfunction "1_1") (pintype "passive"))
      (node (ref "U$1") (pin "57") (pinfunction "PB3/MTIOC0A/MTIOC4A/SCK6_57") (pintype "bidirectional"))
    )
    (net (code "31") (name "/ENC-SW") (class "Default")
      (node (ref "R38") (pin "2") (pinfunction "2_2") (pintype "passive"))
      (node (ref "U$1") (pin "56") (pinfunction "PB4_56") (pintype "bidirectional"))
      (node (ref "U$58") (pin "3") (pinfunction "SW_3") (pintype "bidirectional"))
    )
    (net (code "32") (name "/EXTAL") (class "Default")
      (node (ref "C8") (pin "1") (pinfunction "1_1") (pintype "passive"))
      (node (ref "U$1") (pin "13") (pinfunction "P36/EXTAL_13") (pintype "bidirectional"))
      (node (ref "U$61") (pin "1") (pinfunction "1_1") (pintype "bidirectional"))
    )
    (net (code "33") (name "/IMU_INT") (class "Default")
      (node (ref "U$1") (pin "30") (pinfunction "P16/MTIOC3C/MTIOC3D/TXD1/RXD3_30") (pintype "bidirectional"))
      (node (ref "U$32") (pin "8") (pinfunction "INT_8") (pintype "bidirectional"))
    )
    (net (code "34") (name "/MD") (class "Default")
      (node (ref "LED5") (pin "C") (pinfunction "C_C") (pintype "passive"))
      (node (ref "SJ4") (pin "2") (pinfunction "2_2") (pintype "passive"))
      (node (ref "U$1") (pin "7") (pinfunction "MD/FINED_7") (pintype "bidirectional"))
      (node (ref "U$68") (pin "4") (pinfunction "O_4") (pintype "tri_state"))
      (node (ref "X1") (pin "7") (pinfunction "S_7") (pintype "passive"))
    )
    (net (code "35") (name "/MODE_SW_EN") (class "Default")
      (node (ref "R_MD2") (pin "2") (pinfunction "2_2") (pintype "passive"))
      (node (ref "SJ5") (pin "2") (pinfunction "2_2") (pintype "passive"))
      (node (ref "U$68") (pin "1") (pinfunction "OE_1") (pintype "input"))
    )
    (net (code "36") (name "/MTCLKA") (class "Default")
      (node (ref "U$1") (pin "32") (pinfunction "P14/MTIOC3A/MTCLKA/CTX1_32") (pintype "bidirectional"))
      (node (ref "U$56") (pin "2") (pinfunction "2_2") (pintype "passive"))
    )
    (net (code "37") (name "/MTCLKA_I") (class "Default")
      (node (ref "C2") (pin "1") (pinfunction "1_1") (pintype "passive"))
      (node (ref "D2") (pin "A") (pinfunction "A_A") (pintype "passive"))
      (node (ref "R20") (pin "1") (pinfunction "1_1") (pintype "passive"))
      (node (ref "U$56") (pin "1") (pinfunction "1_1") (pintype "passive"))
    )
    (net (code "38") (name "/MTCLKB") (class "Default")
      (node (ref "U$1") (pin "31") (pinfunction "P15/MTIOC0B/MTCLKB/RXD1/SCK3_31") (pintype "bidirectional"))
      (node (ref "U$59") (pin "2") (pinfunction "2_2") (pintype "passive"))
    )
    (net (code "39") (name "/MTCLKB_I") (class "Default")
      (node (ref "C14") (pin "1") (pinfunction "1_1") (pintype "passive"))
      (node (ref "D3") (pin "A") (pinfunction "A_A") (pintype "passive"))
      (node (ref "R21") (pin "1") (pinfunction "1_1") (pintype "passive"))
      (node (ref "U$59") (pin "1") (pinfunction "1_1") (pintype "passive"))
    )
    (net (code "40") (name "/MTCLKC") (class "Default")
      (node (ref "U$1") (pin "48") (pinfunction "PC4/MTIOC3D/MTCLKC/SCK5_48") (pintype "bidirectional"))
      (node (ref "U$6") (pin "2") (pinfunction "2_2") (pintype "passive"))
    )
    (net (code "41") (name "/MTCLKC_I") (class "Default")
      (node (ref "C13") (pin "1") (pinfunction "1_1") (pintype "passive"))
      (node (ref "D4") (pin "A") (pinfunction "A_A") (pintype "passive"))
      (node (ref "R18") (pin "1") (pinfunction "1_1") (pintype "passive"))
      (node (ref "U$6") (pin "1") (pinfunction "1_1") (pintype "passive"))
    )
    (net (code "42") (name "/MTCLKD") (class "Default")
      (node (ref "U$1") (pin "47") (pinfunction "PC5/MTIOC3B/MTCLKD/SCK8_47") (pintype "bidirectional"))
      (node (ref "U$55") (pin "2") (pinfunction "2_2") (pintype "passive"))
    )
    (net (code "43") (name "/MTCLKD_I") (class "Default")
      (node (ref "C12") (pin "1") (pinfunction "1_1") (pintype "passive"))
      (node (ref "D5") (pin "A") (pinfunction "A_A") (pintype "passive"))
      (node (ref "R19") (pin "1") (pinfunction "1_1") (pintype "passive"))
      (node (ref "U$55") (pin "1") (pinfunction "1_1") (pintype "passive"))
    )
    (net (code "44") (name "/MTIOC4A") (class "Default")
      (node (ref "Q4") (pin "1") (pinfunction "G_1") (pintype "bidirectional"))
      (node (ref "R43") (pin "2") (pinfunction "2_2") (pintype "passive"))
      (node (ref "U$1") (pin "76") (pinfunction "PE2/MTIOC4A/RXD12/AN0_76") (pintype "bidirectional"))
    )
    (net (code "45") (name "/NMCLR") (class "Default")
      (node (ref "IC6") (pin "18") (pinfunction "~{MCLR}_18") (pintype "bidirectional"))
      (node (ref "JP5") (pin "5") (pinfunction "5_5") (pintype "passive"))
      (node (ref "R59") (pin "1") (pinfunction "1_1") (pintype "passive"))
    )
    (net (code "46") (name "/P22") (class "Default")
      (node (ref "R24") (pin "1") (pinfunction "1_1") (pintype "passive"))
      (node (ref "S8") (pin "1") (pinfunction "S_1") (pintype "passive"))
      (node (ref "S8") (pin "2") (pinfunction "S1_2") (pintype "passive"))
      (node (ref "U$1") (pin "26") (pinfunction "P22/MTIOC3B/MTCLKC/SCK0_26") (pintype "bidirectional"))
    )
    (net (code "47") (name "/P23") (class "Default")
      (node (ref "R23") (pin "2") (pinfunction "2_2") (pintype "passive"))
      (node (ref "S7") (pin "1") (pinfunction "S_1") (pintype "passive"))
      (node (ref "S7") (pin "2") (pinfunction "S1_2") (pintype "passive"))
      (node (ref "U$1") (pin "25") (pinfunction "P23/MTIOC3D/MTCLKD/TXD3_25") (pintype "bidirectional"))
    )
    (net (code "48") (name "/P24") (class "Default")
      (node (ref "R32") (pin "1") (pinfunction "1_1") (pintype "passive"))
      (node (ref "S5") (pin "1") (pinfunction "S_1") (pintype "passive"))
      (node (ref "S5") (pin "2") (pinfunction "S1_2") (pintype "passive"))
      (node (ref "U$1") (pin "24") (pinfunction "P24/MTIOC4A/MTCLKA/SCK3_24") (pintype "bidirectional"))
    )
    (net (code "49") (name "/P25") (class "Default")
      (node (ref "R31") (pin "2") (pinfunction "2_2") (pintype "passive"))
      (node (ref "S4") (pin "1") (pinfunction "S_1") (pintype "passive"))
      (node (ref "S4") (pin "2") (pinfunction "S1_2") (pintype "passive"))
      (node (ref "U$1") (pin "23") (pinfunction "P25/MTIOC4C/MTCLKB/RXD3_23") (pintype "bidirectional"))
    )
    (net (code "50") (name "/PA0") (class "Default")
      (node (ref "U$1") (pin "70") (pinfunction "PA0/MTIOC4A_70") (pintype "bidirectional"))
      (node (ref "X3") (pin "3") (pinfunction "S_3") (pintype "passive"))
    )
    (net (code "51") (name "/PA1") (class "Default")
      (node (ref "U$1") (pin "69") (pinfunction "PA1/MTIOC0B/MTCLKC/SCK5_69") (pintype "bidirectional"))
      (node (ref "X3") (pin "4") (pinfunction "S_4") (pintype "passive"))
    )
    (net (code "52") (name "/PA2") (class "Default")
      (node (ref "U$1") (pin "68") (pinfunction "PA2/RXD5_68") (pintype "bidirectional"))
      (node (ref "X3") (pin "5") (pinfunction "S_5") (pintype "passive"))
    )
    (net (code "53") (name "/PA3") (class "Default")
      (node (ref "U$1") (pin "67") (pinfunction "PA3/MTIOC0D/MTCLKD/RXD5_67") (pintype "bidirectional"))
      (node (ref "X3") (pin "6") (pinfunction "S_6") (pintype "passive"))
    )
    (net (code "54") (name "/PA4") (class "Default")
      (node (ref "U$1") (pin "66") (pinfunction "PA4/MTCLKA/TXD5_66") (pintype "bidirectional"))
      (node (ref "X3") (pin "7") (pinfunction "S_7") (pintype "passive"))
    )
    (net (code "55") (name "/PA5") (class "Default")
      (node (ref "U$1") (pin "65") (pinfunction "PA5_65") (pintype "bidirectional"))
      (node (ref "X3") (pin "8") (pinfunction "S_8") (pintype "passive"))
    )
    (net (code "56") (name "/PA6") (class "Default")
      (node (ref "U$1") (pin "64") (pinfunction "PA6/MTCLKB_64") (pintype "bidirectional"))
      (node (ref "X3") (pin "9") (pinfunction "S_9") (pintype "passive"))
    )
    (net (code "57") (name "/PA7") (class "Default")
      (node (ref "U$1") (pin "63") (pinfunction "PA7_63") (pintype "bidirectional"))
      (node (ref "X3") (pin "10") (pinfunction "S_10") (pintype "passive"))
    )
    (net (code "58") (name "/PC7") (class "Default")
      (node (ref "R27") (pin "2") (pinfunction "2_2") (pintype "passive"))
      (node (ref "U$1") (pin "45") (pinfunction "PC7/MTIOC3A/MTCLKB/TXD8_45") (pintype "bidirectional"))
      (node (ref "X1") (pin "10") (pinfunction "S_10") (pintype "passive"))
    )
    (net (code "59") (name "/PE3") (class "Default")
      (node (ref "U$1") (pin "75") (pinfunction "PE3/MTIOC4B/AN1_75") (pintype "bidirectional"))
    )
    (net (code "60") (name "/PE4") (class "Default")
      (node (ref "U$1") (pin "74") (pinfunction "PE4/MTIOC4D/MTIOC1A/AN2_74") (pintype "bidirectional"))
    )
    (net (code "61") (name "/PE5") (class "Default")
      (node (ref "U$1") (pin "73") (pinfunction "PE5/MTIOC4C/MTIOC2B/AN3_73") (pintype "bidirectional"))
    )
    (net (code "62") (name "/PE6") (class "Default")
      (node (ref "U$1") (pin "72") (pinfunction "PE6/AN4_72") (pintype "bidirectional"))
    )
    (net (code "63") (name "/PGEC1") (class "Default")
      (node (ref "IC6") (pin "22") (pinfunction "RB1_22") (pintype "bidirectional"))
      (node (ref "JP5") (pin "1") (pinfunction "1_1") (pintype "passive"))
      (node (ref "SJ4") (pin "1") (pinfunction "1_1") (pintype "passive"))
    )
    (net (code "64") (name "/PGED1") (class "Default")
      (node (ref "IC6") (pin "21") (pinfunction "RB0_21") (pintype "bidirectional"))
      (node (ref "JP5") (pin "2") (pinfunction "2_2") (pintype "passive"))
      (node (ref "SJ5") (pin "1") (pinfunction "1_1") (pintype "passive"))
    )
    (net (code "65") (name "/PIC_DM") (class "Default")
      (node (ref "IC6") (pin "9") (pinfunction "RB11_9") (pintype "bidirectional"))
      (node (ref "U$75") (pin "2") (pinfunction "D-_2") (pintype "bidirectional"))
    )
    (net (code "66") (name "/PIC_DP") (class "Default")
      (node (ref "IC6") (pin "8") (pinfunction "RB10_8") (pintype "bidirectional"))
      (node (ref "U$75") (pin "3") (pinfunction "D+_3") (pintype "bidirectional"))
    )
    (net (code "67") (name "/RB9") (class "Default")
      (node (ref "IC6") (pin "1") (pinfunction "RB9_1") (pintype "bidirectional"))
      (node (ref "SJ1") (pin "2") (pinfunction "2_2") (pintype "passive"))
    )
    (net (code "68") (name "/RES#") (class "Default")
      (node (ref "R15") (pin "1") (pinfunction "1_1") (pintype "passive"))
      (node (ref "S3") (pin "1") (pinfunction "S_1") (pintype "passive"))
      (node (ref "S3") (pin "2") (pinfunction "S1_2") (pintype "passive"))
      (node (ref "SJ1") (pin "1") (pinfunction "1_1") (pintype "passive"))
      (node (ref "U$1") (pin "10") (pinfunction "RES#_10") (pintype "bidirectional"))
      (node (ref "X1") (pin "13") (pinfunction "S_13") (pintype "passive"))
    )
    (net (code "69") (name "/RS") (class "Default")
      (node (ref "U$1") (pin "59") (pinfunction "PB1/MTIOC0C/MTIOC4C/TXD6_59") (pintype "bidirectional"))
    )
    (net (code "70") (name "/RXD0") (class "Default")
      (node (ref "JP3") (pin "1") (pinfunction "1_1") (pintype "passive"))
      (node (ref "U$1") (pin "27") (pinfunction "P21/MTIOC1B/RXD0_27") (pintype "bidirectional"))
    )
    (net (code "71") (name "/RXD1") (class "Default")
      (node (ref "JP7") (pin "3") (pinfunction "3_3") (pintype "passive"))
      (node (ref "U$1") (pin "20") (pinfunction "P30/TDI/MTIOC4B/RXD1_20") (pintype "bidirectional"))
    )
    (net (code "72") (name "/RXD2") (class "Default")
      (node (ref "IC4") (pin "1") (pinfunction "TXD_1") (pintype "output"))
      (node (ref "U$1") (pin "42") (pinfunction "P52/RXD2_42") (pintype "bidirectional"))
    )
    (net (code "73") (name "/SBDBT1-RX") (class "Default")
      (node (ref "IC6") (pin "3") (pinfunction "RC7_3") (pintype "bidirectional"))
      (node (ref "JP7") (pin "2") (pinfunction "2_2") (pintype "passive"))
    )
    (net (code "74") (name "/SBDBT1-TX") (class "Default")
      (node (ref "IC6") (pin "2") (pinfunction "RC6_2") (pintype "bidirectional"))
      (node (ref "JP7") (pin "1") (pinfunction "1_1") (pintype "passive"))
    )
    (net (code "75") (name "/SCL0") (class "Default")
      (node (ref "R25") (pin "2") (pinfunction "2_2") (pintype "passive"))
      (node (ref "U$1") (pin "34") (pinfunction "P12/RXD2_34") (pintype "bidirectional"))
      (node (ref "U$32") (pin "3") (pinfunction "SCL_3") (pintype "bidirectional"))
    )
    (net (code "76") (name "/SDA0") (class "Default")
      (node (ref "R26") (pin "2") (pinfunction "2_2") (pintype "passive"))
      (node (ref "U$1") (pin "33") (pinfunction "P13/MTIOC0B/TXD2_33") (pintype "bidirectional"))
      (node (ref "U$32") (pin "4") (pinfunction "SDA_4") (pintype "bidirectional"))
    )
    (net (code "77") (name "/TCK") (class "Default")
      (node (ref "R8") (pin "2") (pinfunction "2_2") (pintype "passive"))
      (node (ref "U$1") (pin "21") (pinfunction "P27/TCK/MTIOC2B/SCK1_21") (pintype "bidirectional"))
      (node (ref "X1") (pin "1") (pinfunction "S_1") (pintype "passive"))
    )
    (net (code "78") (name "/TMS") (class "Default")
      (node (ref "R11") (pin "2") (pinfunction "2_2") (pintype "passive"))
      (node (ref "U$1") (pin "19") (pinfunction "P31/TMS/MTIOC4D_19") (pintype "bidirectional"))
      (node (ref "X1") (pin "9") (pinfunction "S_9") (pintype "passive"))
    )
    (net (code "79") (name "/TRST#") (class "Default")
      (node (ref "R9") (pin "2") (pinfunction "2_2") (pintype "passive"))
      (node (ref "U$1") (pin "16") (pinfunction "P34/MTIOC0A/SCK6/SCK0/USB0_DPRPD_16") (pintype "bidirectional"))
      (node (ref "X1") (pin "3") (pinfunction "S_3") (pintype "passive"))
    )
    (net (code "80") (name "/TXD0") (class "Default")
      (node (ref "JP3") (pin "2") (pinfunction "2_2") (pintype "passive"))
      (node (ref "U$1") (pin "28") (pinfunction "P20/MTIOC1A/TXD0_28") (pintype "bidirectional"))
    )
    (net (code "81") (name "/TXD1") (class "Default")
      (node (ref "JP7") (pin "4") (pinfunction "4_4") (pintype "passive"))
      (node (ref "U$1") (pin "22") (pinfunction "P26/TDO/MTIOC2A/TXD1_22") (pintype "bidirectional"))
    )
    (net (code "82") (name "/TXD2") (class "Default")
      (node (ref "R16") (pin "2") (pinfunction "2_2") (pintype "passive"))
      (node (ref "U$1") (pin "44") (pinfunction "P50/TXD2_44") (pintype "bidirectional"))
    )
    (net (code "83") (name "/USB0_DM") (class "Default")
      (node (ref "R13") (pin "2") (pinfunction "2_2") (pintype "passive"))
      (node (ref "U$1") (pin "36") (pinfunction "USB0_DM_36") (pintype "bidirectional"))
      (node (ref "U$29") (pin "2") (pinfunction "D-_2") (pintype "bidirectional"))
    )
    (net (code "84") (name "/USB0_DP") (class "Default")
      (node (ref "R14") (pin "2") (pinfunction "2_2") (pintype "passive"))
      (node (ref "U$1") (pin "37") (pinfunction "USB0_DP_37") (pintype "bidirectional"))
      (node (ref "U$29") (pin "3") (pinfunction "D+_3") (pintype "bidirectional"))
    )
    (net (code "85") (name "/VBUS0") (class "Default")
      (node (ref "D1") (pin "C") (pinfunction "C_C") (pintype "passive"))
      (node (ref "U$2") (pin "1") (pinfunction "VBUS_1") (pintype "bidirectional"))
    )
    (net (code "86") (name "/VIN1") (class "Default")
      (node (ref "S6") (pin "2") (pinfunction "P_2") (pintype "passive"))
      (node (ref "U$10") (pin "P$1") (pinfunction "P$1_P$1") (pintype "bidirectional"))
    )
    (net (code "87") (name "/VIN2") (class "Default")
      (node (ref "C4") (pin "2") (pinfunction "2_2") (pintype "passive"))
      (node (ref "S6") (pin "1") (pinfunction "O_1") (pintype "passive"))
      (node (ref "U$11") (pin "VIN@0") (pinfunction "VIN_VIN@0") (pintype "bidirectional"))
      (node (ref "U$11") (pin "VIN@1") (pinfunction "VIN_VIN@1") (pintype "bidirectional"))
    )
    (net (code "88") (name "/XTAL") (class "Default")
      (node (ref "C5") (pin "2") (pinfunction "2_2") (pintype "passive"))
      (node (ref "U$1") (pin "11") (pinfunction "P37/XTAL_11") (pintype "bidirectional"))
      (node (ref "U$61") (pin "3") (pinfunction "3_3") (pintype "bidirectional"))
    )
    (net (code "89") (name "GND") (class "Default")
      (node (ref "C1") (pin "2") (pinfunction "2_2") (pintype "passive"))
      (node (ref "C10") (pin "1") (pinfunction "1_1") (pintype "passive"))
      (node (ref "C11") (pin "1") (pinfunction "1_1") (pintype "passive"))
      (node (ref "C12") (pin "2") (pinfunction "2_2") (pintype "passive"))
      (node (ref "C13") (pin "2") (pinfunction "2_2") (pintype "passive"))
      (node (ref "C14") (pin "2") (pinfunction "2_2") (pintype "passive"))
      (node (ref "C15") (pin "1") (pinfunction "1_1") (pintype "passive"))
      (node (ref "C17") (pin "2") (pinfunction "2_2") (pintype "passive"))
      (node (ref "C2") (pin "2") (pinfunction "2_2") (pintype "passive"))
      (node (ref "C24") (pin "2") (pinfunction "2_2") (pintype "passive"))
      (node (ref "C25") (pin "2") (pinfunction "2_2") (pintype "passive"))
      (node (ref "C3") (pin "2") (pinfunction "2_2") (pintype "passive"))
      (node (ref "C34") (pin "1") (pinfunction "1_1") (pintype "passive"))
      (node (ref "C35") (pin "1") (pinfunction "1_1") (pintype "passive"))
      (node (ref "C4") (pin "1") (pinfunction "1_1") (pintype "passive"))
      (node (ref "C40") (pin "1") (pinfunction "1_1") (pintype "passive"))
      (node (ref "C41") (pin "1") (pinfunction "1_1") (pintype "passive"))
      (node (ref "C42") (pin "1") (pinfunction "1_1") (pintype "passive"))
      (node (ref "C46") (pin "2") (pinfunction "2_2") (pintype "passive"))
      (node (ref "C5") (pin "1") (pinfunction "1_1") (pintype "passive"))
      (node (ref "C6") (pin "1") (pinfunction "1_1") (pintype "passive"))
      (node (ref "C7") (pin "1") (pinfunction "1_1") (pintype "passive"))
      (node (ref "C8") (pin "2") (pinfunction "2_2") (pintype "passive"))
      (node (ref "C9") (pin "1") (pinfunction "1_1") (pintype "passive"))
      (node (ref "IC1") (pin "1") (pinfunction "GND_1") (pintype "power_in"))
      (node (ref "IC4") (pin "18") (pinfunction "GND_18") (pintype "power_in"))
      (node (ref "IC4") (pin "21") (pinfunction "GND_21") (pintype "power_in"))
      (node (ref "IC4") (pin "25") (pinfunction "GND_25") (pintype "power_in"))
      (node (ref "IC4") (pin "26") (pinfunction "TEST_26") (pintype "input"))
      (node (ref "IC4") (pin "7") (pinfunction "GND_7") (pintype "power_in"))
      (node (ref "IC6") (pin "16") (pinfunction "AVSS_16") (pintype "power_in"))
      (node (ref "IC6") (pin "29") (pinfunction "VSS_29") (pintype "power_in"))
      (node (ref "IC6") (pin "39") (pinfunction "VSS_39") (pintype "power_in"))
      (node (ref "IC6") (pin "6") (pinfunction "DISVREG_6") (pintype "passive"))
      (node (ref "JP3") (pin "6") (pinfunction "6_6") (pintype "passive"))
      (node (ref "JP5") (pin "3") (pinfunction "3_3") (pintype "passive"))
      (node (ref "LED1") (pin "C") (pinfunction "C_C") (pintype "passive"))
      (node (ref "LED2") (pin "C") (pinfunction "C_C") (pintype "passive"))
      (node (ref "LED3") (pin "C") (pinfunction "C_C") (pintype "passive"))
      (node (ref "LED4") (pin "C") (pinfunction "C_C") (pintype "passive"))
      (node (ref "Q1") (pin "2") (pinfunction "S_2") (pintype "bidirectional"))
      (node (ref "Q2") (pin "2") (pinfunction "S_2") (pintype "bidirectional"))
      (node (ref "Q3") (pin "2") (pinfunction "S_2") (pintype "bidirectional"))
      (node (ref "Q4") (pin "2") (pinfunction "S_2") (pintype "bidirectional"))
      (node (ref "R27") (pin "1") (pinfunction "1_1") (pintype "passive"))
      (node (ref "R28") (pin "1") (pinfunction "1_1") (pintype "passive"))
      (node (ref "R38") (pin "1") (pinfunction "1_1") (pintype "passive"))
      (node (ref "R40") (pin "2") (pinfunction "2_2") (pintype "passive"))
      (node (ref "R43") (pin "1") (pinfunction "1_1") (pintype "passive"))
      (node (ref "R48") (pin "2") (pinfunction "2_2") (pintype "passive"))
      (node (ref "R49") (pin "2") (pinfunction "2_2") (pintype "passive"))
      (node (ref "R50") (pin "2") (pinfunction "2_2") (pintype "passive"))
      (node (ref "R9") (pin "1") (pinfunction "1_1") (pintype "passive"))
      (node (ref "R_MD2") (pin "1") (pinfunction "1_1") (pintype "passive"))
      (node (ref "R_XCIN") (pin "1") (pinfunction "1_1") (pintype "passive"))
      (node (ref "S3") (pin "3") (pinfunction "P_3") (pintype "passive"))
      (node (ref "S3") (pin "4") (pinfunction "P1_4") (pintype "passive"))
      (node (ref "S4") (pin "3") (pinfunction "P_3") (pintype "passive"))
      (node (ref "S4") (pin "4") (pinfunction "P1_4") (pintype "passive"))
      (node (ref "S5") (pin "3") (pinfunction "P_3") (pintype "passive"))
      (node (ref "S5") (pin "4") (pinfunction "P1_4") (pintype "passive"))
      (node (ref "S7") (pin "3") (pinfunction "P_3") (pintype "passive"))
      (node (ref "S7") (pin "4") (pinfunction "P1_4") (pintype "passive"))
      (node (ref "S8") (pin "3") (pinfunction "P_3") (pintype "passive"))
      (node (ref "S8") (pin "4") (pinfunction "P1_4") (pintype "passive"))
      (node (ref "U$1") (pin "12") (pinfunction "VSS_12") (pintype "bidirectional"))
      (node (ref "U$1") (pin "3") (pinfunction "VREFL_3") (pintype "bidirectional"))
      (node (ref "U$1") (pin "38") (pinfunction "VSS_USB_38") (pintype "bidirectional"))
      (node (ref "U$1") (pin "62") (pinfunction "VSS_62") (pintype "bidirectional"))
      (node (ref "U$1") (pin "94") (pinfunction "VREFL0_94") (pintype "bidirectional"))
      (node (ref "U$1") (pin "99") (pinfunction "AVSS0_99") (pintype "bidirectional"))
      (node (ref "U$10") (pin "P$2") (pinfunction "P$2_P$2") (pintype "bidirectional"))
      (node (ref "U$11") (pin "GND@0") (pinfunction "GND_GND@0") (pintype "bidirectional"))
      (node (ref "U$11") (pin "GND@1") (pinfunction "GND_GND@1") (pintype "bidirectional"))
      (node (ref "U$11") (pin "GND@2") (pinfunction "GND_GND@2") (pintype "bidirectional"))
      (node (ref "U$11") (pin "ON/OFF") (pinfunction "ON/OFF_ON/OFF") (pintype "bidirectional"))
      (node (ref "U$17") (pin "2") (pinfunction "VSS_2") (pintype "power_in"))
      (node (ref "U$17") (pin "8") (pinfunction "STBY_8") (pintype "bidirectional"))
      (node (ref "U$2") (pin "5") (pinfunction "GND_5") (pintype "bidirectional"))
      (node (ref "U$26") (pin "2") (pinfunction "GND_2") (pintype "power_in"))
      (node (ref "U$27") (pin "P$6") (pinfunction "6_P$6") (pintype "passive"))
      (node (ref "U$27") (pin "P$7") (pinfunction "7_P$7") (pintype "passive"))
      (node (ref "U$27") (pin "P$8") (pinfunction "8_P$8") (pintype "passive"))
      (node (ref "U$29") (pin "4") (pinfunction "GND_4") (pintype "bidirectional"))
      (node (ref "U$3") (pin "2") (pinfunction "VSS_2") (pintype "power_in"))
      (node (ref "U$3") (pin "8") (pinfunction "STBY_8") (pintype "bidirectional"))
      (node (ref "U$32") (pin "10") (pinfunction "GND_10") (pintype "bidirectional"))
      (node (ref "U$32") (pin "9") (pinfunction "AD0_9") (pintype "bidirectional"))
      (node (ref "U$4") (pin "P$6") (pinfunction "6_P$6") (pintype "passive"))
      (node (ref "U$4") (pin "P$7") (pinfunction "7_P$7") (pintype "passive"))
      (node (ref "U$4") (pin "P$8") (pinfunction "8_P$8") (pintype "passive"))
      (node (ref "U$5") (pin "P$6") (pinfunction "6_P$6") (pintype "passive"))
      (node (ref "U$5") (pin "P$7") (pinfunction "7_P$7") (pintype "passive"))
      (node (ref "U$5") (pin "P$8") (pinfunction "8_P$8") (pintype "passive"))
      (node (ref "U$58") (pin "7") (pinfunction "C_7") (pintype "bidirectional"))
      (node (ref "U$61") (pin "2") (pinfunction "GND_2") (pintype "power_in"))
      (node (ref "U$61") (pin "4") (pinfunction "GND_4") (pintype "power_in"))
      (node (ref "U$68") (pin "3") (pinfunction "G_3") (pintype "bidirectional"))
      (node (ref "U$75") (pin "4") (pinfunction "GND_4") (pintype "bidirectional"))
      (node (ref "U$8") (pin "K") (pinfunction "K_K") (pintype "bidirectional"))
      (node (ref "U$82") (pin "1") (pinfunction "1_1") (pintype "bidirectional"))
      (node (ref "U$82") (pin "4") (pinfunction "4_4") (pintype "bidirectional"))
      (node (ref "U$9") (pin "P$6") (pinfunction "6_P$6") (pintype "passive"))
      (node (ref "U$9") (pin "P$7") (pinfunction "7_P$7") (pintype "passive"))
      (node (ref "U$9") (pin "P$8") (pinfunction "8_P$8") (pintype "passive"))
      (node (ref "X1") (pin "12") (pinfunction "S_12") (pintype "passive"))
      (node (ref "X1") (pin "14") (pinfunction "S_14") (pintype "passive"))
      (node (ref "X1") (pin "2") (pinfunction "S_2") (pintype "passive"))
      (node (ref "X2") (pin "2") (pinfunction "S_2") (pintype "passive"))
      (node (ref "X3") (pin "2") (pinfunction "S_2") (pintype "passive"))
      (node (ref "X4") (pin "2") (pinfunction "2_2") (pintype "bidirectional"))
      (node (ref "X5") (pin "2") (pinfunction "2_2") (pintype "bidirectional"))
    )
    (net (code "90") (name "Net-(D2-PadC)") (class "Default")
      (node (ref "D2") (pin "C") (pinfunction "C_C") (pintype "passive"))
      (node (ref "X5") (pin "3") (pinfunction "3_3") (pintype "bidirectional"))
    )
    (net (code "91") (name "Net-(D3-PadC)") (class "Default")
      (node (ref "D3") (pin "C") (pinfunction "C_C") (pintype "passive"))
      (node (ref "X5") (pin "4") (pinfunction "4_4") (pintype "bidirectional"))
    )
    (net (code "92") (name "Net-(D4-PadC)") (class "Default")
      (node (ref "D4") (pin "C") (pinfunction "C_C") (pintype "passive"))
      (node (ref "X4") (pin "3") (pinfunction "3_3") (pintype "bidirectional"))
    )
    (net (code "93") (name "Net-(D5-PadC)") (class "Default")
      (node (ref "D5") (pin "C") (pinfunction "C_C") (pintype "passive"))
      (node (ref "X4") (pin "4") (pinfunction "4_4") (pintype "bidirectional"))
    )
    (net (code "94") (name "Net-(IC1-~{RES})") (class "Default")
      (node (ref "IC1") (pin "2") (pinfunction "~{RES}_2") (pintype "output"))
      (node (ref "R15") (pin "2") (pinfunction "2_2") (pintype "passive"))
    )
    (net (code "95") (name "Net-(IC4-3V3OUT)") (class "Default")
      (node (ref "C9") (pin "2") (pinfunction "2_2") (pintype "passive"))
      (node (ref "IC4") (pin "17") (pinfunction "3V3OUT_17") (pintype "output"))
      (node (ref "IC4") (pin "4") (pinfunction "VCCIO_4") (pintype "power_in"))
    )
    (net (code "96") (name "Net-(IC4-RXD)") (class "Default")
      (node (ref "IC4") (pin "5") (pinfunction "RXD_5") (pintype "input"))
      (node (ref "R16") (pin "1") (pinfunction "1_1") (pintype "passive"))
    )
    (net (code "97") (name "Net-(IC4-USBDM)") (class "Default")
      (node (ref "IC4") (pin "16") (pinfunction "USBDM_16") (pintype "bidirectional"))
      (node (ref "U$2") (pin "2") (pinfunction "D-_2") (pintype "bidirectional"))
    )
    (net (code "98") (name "Net-(IC4-USBDP)") (class "Default")
      (node (ref "IC4") (pin "15") (pinfunction "USBDP_15") (pintype "bidirectional"))
      (node (ref "U$2") (pin "3") (pinfunction "D+_3") (pintype "bidirectional"))
    )
    (net (code "99") (name "Net-(IC6-RB14)") (class "Default")
      (node (ref "IC6") (pin "14") (pinfunction "RB14_14") (pintype "bidirectional"))
      (node (ref "LED9") (pin "A") (pinfunction "A_A") (pintype "passive"))
    )
    (net (code "100") (name "Net-(IC6-RB15)") (class "Default")
      (node (ref "IC6") (pin "15") (pinfunction "RB15_15") (pintype "bidirectional"))
      (node (ref "LED8") (pin "A") (pinfunction "A_A") (pintype "passive"))
    )
    (net (code "101") (name "Net-(IC6-VDDCORE)") (class "Default")
      (node (ref "C40") (pin "2") (pinfunction "2_2") (pintype "passive"))
      (node (ref "IC6") (pin "7") (pinfunction "VDDCORE_7") (pintype "power_in"))
    )
    (net (code "102") (name "Net-(JP1-Pad1)") (class "Default")
      (node (ref "JP1") (pin "1") (pinfunction "1_1") (pintype "passive"))
      (node (ref "R4") (pin "2") (pinfunction "2_2") (pintype "passive"))
    )
    (net (code "103") (name "Net-(JP2-Pad1)") (class "Default")
      (node (ref "JP2") (pin "1") (pinfunction "1_1") (pintype "passive"))
      (node (ref "R3") (pin "2") (pinfunction "2_2") (pintype "passive"))
    )
    (net (code "104") (name "Net-(LED1-PadA)") (class "Default")
      (node (ref "LED1") (pin "A") (pinfunction "A_A") (pintype "passive"))
      (node (ref "R5") (pin "1") (pinfunction "1_1") (pintype "passive"))
    )
    (net (code "105") (name "Net-(LED2-PadA)") (class "Default")
      (node (ref "LED2") (pin "A") (pinfunction "A_A") (pintype "passive"))
      (node (ref "R6") (pin "1") (pinfunction "1_1") (pintype "passive"))
    )
    (net (code "106") (name "Net-(LED3-PadA)") (class "Default")
      (node (ref "LED3") (pin "A") (pinfunction "A_A") (pintype "passive"))
      (node (ref "R7") (pin "1") (pinfunction "1_1") (pintype "passive"))
    )
    (net (code "107") (name "Net-(LED4-PadA)") (class "Default")
      (node (ref "LED4") (pin "A") (pinfunction "A_A") (pintype "passive"))
      (node (ref "R12") (pin "1") (pinfunction "1_1") (pintype "passive"))
    )
    (net (code "108") (name "Net-(LED5-PadA)") (class "Default")
      (node (ref "LED5") (pin "A") (pinfunction "A_A") (pintype "passive"))
      (node (ref "R_MD3") (pin "1") (pinfunction "1_1") (pintype "passive"))
    )
    (net (code "109") (name "Net-(LED8-PadC)") (class "Default")
      (node (ref "LED8") (pin "C") (pinfunction "C_C") (pintype "passive"))
      (node (ref "R57") (pin "1") (pinfunction "1_1") (pintype "passive"))
    )
    (net (code "110") (name "Net-(LED9-PadC)") (class "Default")
      (node (ref "LED9") (pin "C") (pinfunction "C_C") (pintype "passive"))
      (node (ref "R58") (pin "1") (pinfunction "1_1") (pintype "passive"))
    )
    (net (code "111") (name "Net-(Q1-D)") (class "Default")
      (node (ref "Q1") (pin "3") (pinfunction "D_3") (pintype "bidirectional"))
      (node (ref "R45") (pin "1") (pinfunction "1_1") (pintype "passive"))
    )
    (net (code "112") (name "Net-(Q2-D)") (class "Default")
      (node (ref "Q2") (pin "3") (pinfunction "D_3") (pintype "bidirectional"))
      (node (ref "R46") (pin "1") (pinfunction "1_1") (pintype "passive"))
    )
    (net (code "113") (name "Net-(Q3-D)") (class "Default")
      (node (ref "Q3") (pin "3") (pinfunction "D_3") (pintype "bidirectional"))
      (node (ref "R47") (pin "1") (pinfunction "1_1") (pintype "passive"))
    )
    (net (code "114") (name "Net-(Q4-D)") (class "Default")
      (node (ref "Q4") (pin "3") (pinfunction "D_3") (pintype "bidirectional"))
      (node (ref "SG2") (pin "2") (pinfunction "2_2") (pintype "passive"))
    )
    (net (code "115") (name "Net-(R22-Pad2)") (class "Default")
      (node (ref "R22") (pin "2") (pinfunction "2_2") (pintype "passive"))
      (node (ref "U$7") (pin "3") (pinfunction "3_3") (pintype "bidirectional"))
      (node (ref "U$7") (pin "6") (pinfunction "6_6") (pintype "bidirectional"))
    )
    (net (code "116") (name "Net-(R28-Pad2)") (class "Default")
      (node (ref "R28") (pin "2") (pinfunction "2_2") (pintype "passive"))
      (node (ref "U$7") (pin "1") (pinfunction "1_1") (pintype "bidirectional"))
      (node (ref "U$7") (pin "4") (pinfunction "4_4") (pintype "bidirectional"))
    )
    (net (code "117") (name "Net-(R40-Pad1)") (class "Default")
      (node (ref "R40") (pin "1") (pinfunction "1_1") (pintype "passive"))
      (node (ref "U$11") (pin "TRIM") (pinfunction "TRIM_TRIM") (pintype "bidirectional"))
    )
    (net (code "118") (name "Net-(R41-Pad2)") (class "Default")
      (node (ref "R41") (pin "2") (pinfunction "2_2") (pintype "passive"))
      (node (ref "U$8") (pin "A") (pinfunction "A_A") (pintype "bidirectional"))
    )
    (net (code "119") (name "Net-(R_MD4-Pad2)") (class "Default")
      (node (ref "R_MD4") (pin "2") (pinfunction "2_2") (pintype "passive"))
      (node (ref "U$82") (pin "3") (pinfunction "3_3") (pintype "bidirectional"))
      (node (ref "U$82") (pin "6") (pinfunction "6_6") (pintype "bidirectional"))
    )
    (net (code "120") (name "Net-(U$1-P35{slash}NMI)") (class "Default")
      (node (ref "R_NMI") (pin "2") (pinfunction "2_2") (pintype "passive"))
      (node (ref "U$1") (pin "15") (pinfunction "P35/NMI_15") (pintype "bidirectional"))
    )
    (net (code "121") (name "Net-(U$1-PD6{slash}AN6)") (class "Default")
      (node (ref "R7") (pin "2") (pinfunction "2_2") (pintype "passive"))
      (node (ref "U$1") (pin "80") (pinfunction "PD6/AN6_80") (pintype "bidirectional"))
    )
    (net (code "122") (name "Net-(U$1-PD7{slash}AN7)") (class "Default")
      (node (ref "R12") (pin "2") (pinfunction "2_2") (pintype "passive"))
      (node (ref "U$1") (pin "79") (pinfunction "PD7/AN7_79") (pintype "bidirectional"))
    )
    (net (code "123") (name "Net-(U$1-PE0{slash}SCK12{slash}ANEX0)") (class "Default")
      (node (ref "R6") (pin "2") (pinfunction "2_2") (pintype "passive"))
      (node (ref "U$1") (pin "78") (pinfunction "PE0/SCK12/ANEX0_78") (pintype "bidirectional"))
    )
    (net (code "124") (name "Net-(U$1-PE1{slash}MTIOC4C{slash}TXD12{slash}ANEX1)") (class "Default")
      (node (ref "R5") (pin "2") (pinfunction "2_2") (pintype "passive"))
      (node (ref "U$1") (pin "77") (pinfunction "PE1/MTIOC4C/TXD12/ANEX1_77") (pintype "bidirectional"))
    )
    (net (code "125") (name "Net-(U$1-VCL)") (class "Default")
      (node (ref "C1") (pin "1") (pinfunction "1_1") (pintype "passive"))
      (node (ref "U$1") (pin "5") (pinfunction "VCL_5") (pintype "bidirectional"))
    )
    (net (code "126") (name "Net-(U$1-XCIN)") (class "Default")
      (node (ref "R_XCIN") (pin "2") (pinfunction "2_2") (pintype "passive"))
      (node (ref "U$1") (pin "8") (pinfunction "XCIN_8") (pintype "bidirectional"))
    )
    (net (code "127") (name "Net-(U$3-CANH)") (class "Default")
      (node (ref "JP1") (pin "2") (pinfunction "2_2") (pintype "passive"))
      (node (ref "U$3") (pin "7") (pinfunction "CANH_7") (pintype "bidirectional"))
      (node (ref "U$4") (pin "P$5") (pinfunction "5_P$5") (pintype "passive"))
      (node (ref "U$5") (pin "P$5") (pinfunction "5_P$5") (pintype "passive"))
    )
    (net (code "128") (name "Net-(U$3-CANL)") (class "Default")
      (node (ref "R4") (pin "1") (pinfunction "1_1") (pintype "passive"))
      (node (ref "U$3") (pin "6") (pinfunction "CANL_6") (pintype "bidirectional"))
      (node (ref "U$4") (pin "P$4") (pinfunction "4_P$4") (pintype "passive"))
      (node (ref "U$5") (pin "P$4") (pinfunction "4_P$4") (pintype "passive"))
    )
    (net (code "129") (name "Net-(U$17-CANH)") (class "Default")
      (node (ref "JP2") (pin "2") (pinfunction "2_2") (pintype "passive"))
      (node (ref "U$17") (pin "7") (pinfunction "CANH_7") (pintype "bidirectional"))
      (node (ref "U$27") (pin "P$5") (pinfunction "5_P$5") (pintype "passive"))
      (node (ref "U$9") (pin "P$5") (pinfunction "5_P$5") (pintype "passive"))
    )
    (net (code "130") (name "Net-(U$17-CANL)") (class "Default")
      (node (ref "R3") (pin "1") (pinfunction "1_1") (pintype "passive"))
      (node (ref "U$17") (pin "6") (pinfunction "CANL_6") (pintype "bidirectional"))
      (node (ref "U$27") (pin "P$4") (pinfunction "4_P$4") (pintype "passive"))
      (node (ref "U$9") (pin "P$4") (pinfunction "4_P$4") (pintype "passive"))
    )
    (net (code "131") (name "Net-(U$58-BLUE)") (class "Default")
      (node (ref "R47") (pin "2") (pinfunction "2_2") (pintype "passive"))
      (node (ref "U$58") (pin "4") (pinfunction "BLUE_4") (pintype "bidirectional"))
    )
    (net (code "132") (name "Net-(U$58-GREEN)") (class "Default")
      (node (ref "R46") (pin "2") (pinfunction "2_2") (pintype "passive"))
      (node (ref "U$58") (pin "2") (pinfunction "GREEN_2") (pintype "bidirectional"))
    )
    (net (code "133") (name "Net-(U$58-RED)") (class "Default")
      (node (ref "R45") (pin "2") (pinfunction "2_2") (pintype "passive"))
      (node (ref "U$58") (pin "1") (pinfunction "RED_1") (pintype "bidirectional"))
    )
    (net (code "134") (name "Net-(U$68A-I)") (class "Default")
      (node (ref "U$68") (pin "2") (pinfunction "I_2") (pintype "input"))
      (node (ref "U$82") (pin "2") (pinfunction "2_2") (pintype "bidirectional"))
      (node (ref "U$82") (pin "5") (pinfunction "5_5") (pintype "bidirectional"))
    )
    (net (code "135") (name "Net-(U$75-VBUS)") (class "Default")
      (node (ref "U$75") (pin "1") (pinfunction "VBUS_1") (pintype "bidirectional"))
      (node (ref "U$76") (pin "1") (pinfunction "1_1") (pintype "passive"))
    )
    (net (code "136") (name "Net-(X2B-S)") (class "Default")
      (node (ref "U$40") (pin "1") (pinfunction "1_1") (pintype "passive"))
      (node (ref "X2") (pin "10") (pinfunction "S_10") (pintype "passive"))
    )
    (net (code "137") (name "Net-(X2C-S)") (class "Default")
      (node (ref "U$41") (pin "1") (pinfunction "1_1") (pintype "passive"))
      (node (ref "X2") (pin "11") (pinfunction "S_11") (pintype "passive"))
    )
    (net (code "138") (name "Net-(X2D-S)") (class "Default")
      (node (ref "U$42") (pin "1") (pinfunction "1_1") (pintype "passive"))
      (node (ref "X2") (pin "12") (pinfunction "S_12") (pintype "passive"))
    )
    (net (code "139") (name "Net-(X2E-S)") (class "Default")
      (node (ref "U$43") (pin "1") (pinfunction "1_1") (pintype "passive"))
      (node (ref "X2") (pin "13") (pinfunction "S_13") (pintype "passive"))
    )
    (net (code "140") (name "Net-(X2F-S)") (class "Default")
      (node (ref "U$44") (pin "1") (pinfunction "1_1") (pintype "passive"))
      (node (ref "X2") (pin "14") (pinfunction "S_14") (pintype "passive"))
    )
    (net (code "141") (name "Net-(X2G-S)") (class "Default")
      (node (ref "U$45") (pin "1") (pinfunction "1_1") (pintype "passive"))
      (node (ref "X2") (pin "15") (pinfunction "S_15") (pintype "passive"))
    )
    (net (code "142") (name "Net-(X2H-S)") (class "Default")
      (node (ref "U$46") (pin "1") (pinfunction "1_1") (pintype "passive"))
      (node (ref "X2") (pin "16") (pinfunction "S_16") (pintype "passive"))
    )
    (net (code "143") (name "Net-(X2J-S)") (class "Default")
      (node (ref "U$33") (pin "1") (pinfunction "1_1") (pintype "passive"))
      (node (ref "X2") (pin "3") (pinfunction "S_3") (pintype "passive"))
    )
    (net (code "144") (name "Net-(X2K-S)") (class "Default")
      (node (ref "U$34") (pin "1") (pinfunction "1_1") (pintype "passive"))
      (node (ref "X2") (pin "4") (pinfunction "S_4") (pintype "passive"))
    )
    (net (code "145") (name "Net-(X2L-S)") (class "Default")
      (node (ref "U$35") (pin "1") (pinfunction "1_1") (pintype "passive"))
      (node (ref "X2") (pin "5") (pinfunction "S_5") (pintype "passive"))
    )
    (net (code "146") (name "Net-(X2M-S)") (class "Default")
      (node (ref "U$36") (pin "1") (pinfunction "1_1") (pintype "passive"))
      (node (ref "X2") (pin "6") (pinfunction "S_6") (pintype "passive"))
    )
    (net (code "147") (name "Net-(X2N-S)") (class "Default")
      (node (ref "U$37") (pin "1") (pinfunction "1_1") (pintype "passive"))
      (node (ref "X2") (pin "7") (pinfunction "S_7") (pintype "passive"))
    )
    (net (code "148") (name "Net-(X2O-S)") (class "Default")
      (node (ref "U$38") (pin "1") (pinfunction "1_1") (pintype "passive"))
      (node (ref "X2") (pin "8") (pinfunction "S_8") (pintype "passive"))
    )
    (net (code "149") (name "Net-(X2P-S)") (class "Default")
      (node (ref "U$39") (pin "1") (pinfunction "1_1") (pintype "passive"))
      (node (ref "X2") (pin "9") (pinfunction "S_9") (pintype "passive"))
    )
    (net (code "150") (name "VCC") (class "Default")
      (node (ref "C10") (pin "2") (pinfunction "2_2") (pintype "passive"))
      (node (ref "C11") (pin "2") (pinfunction "2_2") (pintype "passive"))
      (node (ref "C3") (pin "1") (pinfunction "1_1") (pintype "passive"))
      (node (ref "C34") (pin "2") (pinfunction "2_2") (pintype "passive"))
      (node (ref "C6") (pin "2") (pinfunction "2_2") (pintype "passive"))
      (node (ref "C7") (pin "2") (pinfunction "2_2") (pintype "passive"))
      (node (ref "D1") (pin "A") (pinfunction "A_A") (pintype "passive"))
      (node (ref "IC4") (pin "20") (pinfunction "VCC_20") (pintype "power_in"))
      (node (ref "IC6") (pin "42") (pinfunction "RB6_42") (pintype "bidirectional"))
      (node (ref "R41") (pin "1") (pinfunction "1_1") (pintype "passive"))
      (node (ref "SG2") (pin "1") (pinfunction "1_1") (pintype "passive"))
      (node (ref "U$11") (pin "SENSE") (pinfunction "SENSE_SENSE") (pintype "bidirectional"))
      (node (ref "U$11") (pin "VOUT") (pinfunction "VOUT_VOUT") (pintype "bidirectional"))
      (node (ref "U$17") (pin "3") (pinfunction "VDD_3") (pintype "power_in"))
      (node (ref "U$26") (pin "1") (pinfunction "IN_1") (pintype "power_in"))
      (node (ref "U$27") (pin "P$1") (pinfunction "1_P$1") (pintype "passive"))
      (node (ref "U$27") (pin "P$2") (pinfunction "2_P$2") (pintype "passive"))
      (node (ref "U$27") (pin "P$3") (pinfunction "3_P$3") (pintype "passive"))
      (node (ref "U$29") (pin "1") (pinfunction "VBUS_1") (pintype "bidirectional"))
      (node (ref "U$3") (pin "3") (pinfunction "VDD_3") (pintype "power_in"))
      (node (ref "U$4") (pin "P$1") (pinfunction "1_P$1") (pintype "passive"))
      (node (ref "U$4") (pin "P$2") (pinfunction "2_P$2") (pintype "passive"))
      (node (ref "U$4") (pin "P$3") (pinfunction "3_P$3") (pintype "passive"))
      (node (ref "U$5") (pin "P$1") (pinfunction "1_P$1") (pintype "passive"))
      (node (ref "U$5") (pin "P$2") (pinfunction "2_P$2") (pintype "passive"))
      (node (ref "U$5") (pin "P$3") (pinfunction "3_P$3") (pintype "passive"))
      (node (ref "U$76") (pin "2") (pinfunction "2_2") (pintype "passive"))
      (node (ref "U$9") (pin "P$1") (pinfunction "1_P$1") (pintype "passive"))
      (node (ref "U$9") (pin "P$2") (pinfunction "2_P$2") (pintype "passive"))
      (node (ref "U$9") (pin "P$3") (pinfunction "3_P$3") (pintype "passive"))
      (node (ref "X4") (pin "1") (pinfunction "1_1") (pintype "bidirectional"))
      (node (ref "X5") (pin "1") (pinfunction "1_1") (pintype "bidirectional"))
    )
    (net (code "151") (name "unconnected-(IC4-CBUS0-Pad23)") (class "Default")
      (node (ref "IC4") (pin "23") (pinfunction "CBUS0_23") (pintype "bidirectional"))
    )
    (net (code "152") (name "unconnected-(IC4-CBUS1-Pad22)") (class "Default")
      (node (ref "IC4") (pin "22") (pinfunction "CBUS1_22") (pintype "bidirectional"))
    )
    (net (code "153") (name "unconnected-(IC4-CBUS2-Pad13)") (class "Default")
      (node (ref "IC4") (pin "13") (pinfunction "CBUS2_13") (pintype "bidirectional"))
    )
    (net (code "154") (name "unconnected-(IC4-CBUS3-Pad14)") (class "Default")
      (node (ref "IC4") (pin "14") (pinfunction "CBUS3_14") (pintype "bidirectional"))
    )
    (net (code "155") (name "unconnected-(IC4-CBUS4-Pad12)") (class "Default")
      (node (ref "IC4") (pin "12") (pinfunction "CBUS4_12") (pintype "bidirectional"))
    )
    (net (code "156") (name "unconnected-(IC4-OSCI-Pad27)") (class "Default")
      (node (ref "IC4") (pin "27") (pinfunction "OSCI_27") (pintype "input"))
    )
    (net (code "157") (name "unconnected-(IC4-OSCO-Pad28)") (class "Default")
      (node (ref "IC4") (pin "28") (pinfunction "OSCO_28") (pintype "output"))
    )
    (net (code "158") (name "unconnected-(IC4-~{CTS}-Pad11)") (class "Default")
      (node (ref "IC4") (pin "11") (pinfunction "~{CTS}_11") (pintype "input"))
    )
    (net (code "159") (name "unconnected-(IC4-~{DCD}-Pad10)") (class "Default")
      (node (ref "IC4") (pin "10") (pinfunction "~{DCD}_10") (pintype "input"))
    )
    (net (code "160") (name "unconnected-(IC4-~{DSR}-Pad9)") (class "Default")
      (node (ref "IC4") (pin "9") (pinfunction "~{DSR}_9") (pintype "input"))
    )
    (net (code "161") (name "unconnected-(IC4-~{DTR}-Pad2)") (class "Default")
      (node (ref "IC4") (pin "2") (pinfunction "~{DTR}_2") (pintype "output"))
    )
    (net (code "162") (name "unconnected-(IC4-~{RESET}-Pad19)") (class "Default")
      (node (ref "IC4") (pin "19") (pinfunction "~{RESET}_19") (pintype "input"))
    )
    (net (code "163") (name "unconnected-(IC4-~{RI}-Pad6)") (class "Default")
      (node (ref "IC4") (pin "6") (pinfunction "~{RI}_6") (pintype "input"))
    )
    (net (code "164") (name "unconnected-(IC4-~{RTS}-Pad3)") (class "Default")
      (node (ref "IC4") (pin "3") (pinfunction "~{RTS}_3") (pintype "output"))
    )
    (net (code "165") (name "unconnected-(IC6-RA0-Pad19)") (class "Default")
      (node (ref "IC6") (pin "19") (pinfunction "RA0_19") (pintype "bidirectional"))
    )
    (net (code "166") (name "unconnected-(IC6-RA1-Pad20)") (class "Default")
      (node (ref "IC6") (pin "20") (pinfunction "RA1_20") (pintype "bidirectional"))
    )
    (net (code "167") (name "unconnected-(IC6-RA2-Pad30)") (class "Default")
      (node (ref "IC6") (pin "30") (pinfunction "RA2_30") (pintype "bidirectional"))
    )
    (net (code "168") (name "unconnected-(IC6-RA3-Pad31)") (class "Default")
      (node (ref "IC6") (pin "31") (pinfunction "RA3_31") (pintype "bidirectional"))
    )
    (net (code "169") (name "unconnected-(IC6-RA4-Pad34)") (class "Default")
      (node (ref "IC6") (pin "34") (pinfunction "RA4_34") (pintype "bidirectional"))
    )
    (net (code "170") (name "unconnected-(IC6-RB2-Pad23)") (class "Default")
      (node (ref "IC6") (pin "23") (pinfunction "RB2_23") (pintype "bidirectional"))
    )
    (net (code "171") (name "unconnected-(IC6-RB3-Pad24)") (class "Default")
      (node (ref "IC6") (pin "24") (pinfunction "RB3_24") (pintype "bidirectional"))
    )
    (net (code "172") (name "unconnected-(IC6-RB4-Pad33)") (class "Default")
      (node (ref "IC6") (pin "33") (pinfunction "RB4_33") (pintype "bidirectional"))
    )
    (net (code "173") (name "unconnected-(IC6-RB5-Pad41)") (class "Default")
      (node (ref "IC6") (pin "41") (pinfunction "RB5_41") (pintype "bidirectional"))
    )
    (net (code "174") (name "unconnected-(IC6-RB7-Pad43)") (class "Default")
      (node (ref "IC6") (pin "43") (pinfunction "RB7_43") (pintype "bidirectional"))
    )
    (net (code "175") (name "unconnected-(IC6-RB8-Pad44)") (class "Default")
      (node (ref "IC6") (pin "44") (pinfunction "RB8_44") (pintype "bidirectional"))
    )
    (net (code "176") (name "unconnected-(IC6-RB13-Pad11)") (class "Default")
      (node (ref "IC6") (pin "11") (pinfunction "RB13_11") (pintype "bidirectional"))
    )
    (net (code "177") (name "unconnected-(IC6-RC0-Pad25)") (class "Default")
      (node (ref "IC6") (pin "25") (pinfunction "RC0_25") (pintype "bidirectional"))
    )
    (net (code "178") (name "unconnected-(IC6-RC1-Pad26)") (class "Default")
      (node (ref "IC6") (pin "26") (pinfunction "RC1_26") (pintype "bidirectional"))
    )
    (net (code "179") (name "unconnected-(IC6-RC2-Pad27)") (class "Default")
      (node (ref "IC6") (pin "27") (pinfunction "RC2_27") (pintype "bidirectional"))
    )
    (net (code "180") (name "unconnected-(IC6-RC3-Pad36)") (class "Default")
      (node (ref "IC6") (pin "36") (pinfunction "RC3_36") (pintype "bidirectional"))
    )
    (net (code "181") (name "unconnected-(IC6-RC4-Pad37)") (class "Default")
      (node (ref "IC6") (pin "37") (pinfunction "RC4_37") (pintype "bidirectional"))
    )
    (net (code "182") (name "unconnected-(IC6-RC5-Pad38)") (class "Default")
      (node (ref "IC6") (pin "38") (pinfunction "RC5_38") (pintype "bidirectional"))
    )
    (net (code "183") (name "unconnected-(IC6-TCK-Pad13)") (class "Default")
      (node (ref "IC6") (pin "13") (pinfunction "TCK_13") (pintype "input"))
    )
    (net (code "184") (name "unconnected-(IC6-TDI-Pad35)") (class "Default")
      (node (ref "IC6") (pin "35") (pinfunction "TDI_35") (pintype "input"))
    )
    (net (code "185") (name "unconnected-(IC6-TDO-Pad32)") (class "Default")
      (node (ref "IC6") (pin "32") (pinfunction "TDO_32") (pintype "output"))
    )
    (net (code "186") (name "unconnected-(IC6-TMS-Pad12)") (class "Default")
      (node (ref "IC6") (pin "12") (pinfunction "TMS_12") (pintype "input"))
    )
    (net (code "187") (name "unconnected-(S6-S-Pad3)") (class "Default")
      (node (ref "S6") (pin "3") (pinfunction "S_3") (pintype "passive"))
    )
    (net (code "188") (name "unconnected-(U$1-P05{slash}DA1-Pad100)") (class "Default")
      (node (ref "U$1") (pin "100") (pinfunction "P05/DA1_100") (pintype "bidirectional"))
    )
    (net (code "189") (name "unconnected-(U$1-P07-Pad98)") (class "Default")
      (node (ref "U$1") (pin "98") (pinfunction "P07_98") (pintype "bidirectional"))
    )
    (net (code "190") (name "unconnected-(U$1-P17{slash}MTIOC3A{slash}MTIOC3B{slash}SCK1{slash}TXD3-Pad29)") (class "Default")
      (node (ref "U$1") (pin "29") (pinfunction "P17/MTIOC3A/MTIOC3B/SCK1/TXD3_29") (pintype "bidirectional"))
    )
    (net (code "191") (name "unconnected-(U$1-P51{slash}SCK2-Pad43)") (class "Default")
      (node (ref "U$1") (pin "43") (pinfunction "P51/SCK2_43") (pintype "bidirectional"))
    )
    (net (code "192") (name "unconnected-(U$1-P53{slash}BCLK-Pad41)") (class "Default")
      (node (ref "U$1") (pin "41") (pinfunction "P53/BCLK_41") (pintype "bidirectional"))
    )
    (net (code "193") (name "unconnected-(U$1-PB0{slash}RXD6-Pad61)") (class "Default")
      (node (ref "U$1") (pin "61") (pinfunction "PB0/RXD6_61") (pintype "bidirectional"))
    )
    (net (code "194") (name "unconnected-(U$1-PB6{slash}MTIOC3D{slash}RXD9-Pad54)") (class "Default")
      (node (ref "U$1") (pin "54") (pinfunction "PB6/MTIOC3D/RXD9_54") (pintype "bidirectional"))
    )
    (net (code "195") (name "unconnected-(U$1-PC2{slash}MTIOC4B{slash}TCLKA{slash}RXD5-Pad50)") (class "Default")
      (node (ref "U$1") (pin "50") (pinfunction "PC2/MTIOC4B/TCLKA/RXD5_50") (pintype "bidirectional"))
    )
    (net (code "196") (name "unconnected-(U$1-PC3{slash}MTIOC4D{slash}TCLKB{slash}TXD5-Pad49)") (class "Default")
      (node (ref "U$1") (pin "49") (pinfunction "PC3/MTIOC4D/TCLKB/TXD5_49") (pintype "bidirectional"))
    )
    (net (code "197") (name "unconnected-(U$1-PC6{slash}MTIOC3C{slash}MTCLKA{slash}RXD8-Pad46)") (class "Default")
      (node (ref "U$1") (pin "46") (pinfunction "PC6/MTIOC3C/MTCLKA/RXD8_46") (pintype "bidirectional"))
    )
    (net (code "198") (name "unconnected-(U$1-PE7{slash}AN5-Pad71)") (class "Default")
      (node (ref "U$1") (pin "71") (pinfunction "PE7/AN5_71") (pintype "bidirectional"))
    )
    (net (code "199") (name "unconnected-(U$1-PJ3{slash}MITIOC3C-Pad4)") (class "Default")
      (node (ref "U$1") (pin "4") (pinfunction "PJ3/MITIOC3C_4") (pintype "bidirectional"))
    )
    (net (code "200") (name "unconnected-(U$1-XCOUT-Pad9)") (class "Default")
      (node (ref "U$1") (pin "9") (pinfunction "XCOUT_9") (pintype "bidirectional"))
    )
    (net (code "201") (name "unconnected-(U$2-ID(NC)-Pad4)") (class "Default")
      (node (ref "U$2") (pin "4") (pinfunction "ID(NC)_4") (pintype "bidirectional"))
    )
    (net (code "202") (name "unconnected-(U$11-PadPGOOD)") (class "Default")
      (node (ref "U$11") (pin "PGOOD") (pinfunction "PGOOD_PGOOD") (pintype "bidirectional"))
    )
    (net (code "203") (name "unconnected-(U$32-ES_CL-Pad6)") (class "Default")
      (node (ref "U$32") (pin "6") (pinfunction "ES_CL_6") (pintype "bidirectional"))
    )
    (net (code "204") (name "unconnected-(U$32-ES_DA-Pad5)") (class "Default")
      (node (ref "U$32") (pin "5") (pinfunction "ES_DA_5") (pintype "bidirectional"))
    )
    (net (code "205") (name "unconnected-(U$32-FSYNC-Pad7)") (class "Default")
      (node (ref "U$32") (pin "7") (pinfunction "FSYNC_7") (pintype "bidirectional"))
    )
    (net (code "206") (name "unconnected-(X1K-S-Pad6)") (class "Default")
      (node (ref "X1") (pin "6") (pinfunction "S_6") (pintype "passive"))
    )
  )
)
